# io-board-c-6.net
KiCad netlist of a schematic drawn in EAGLE
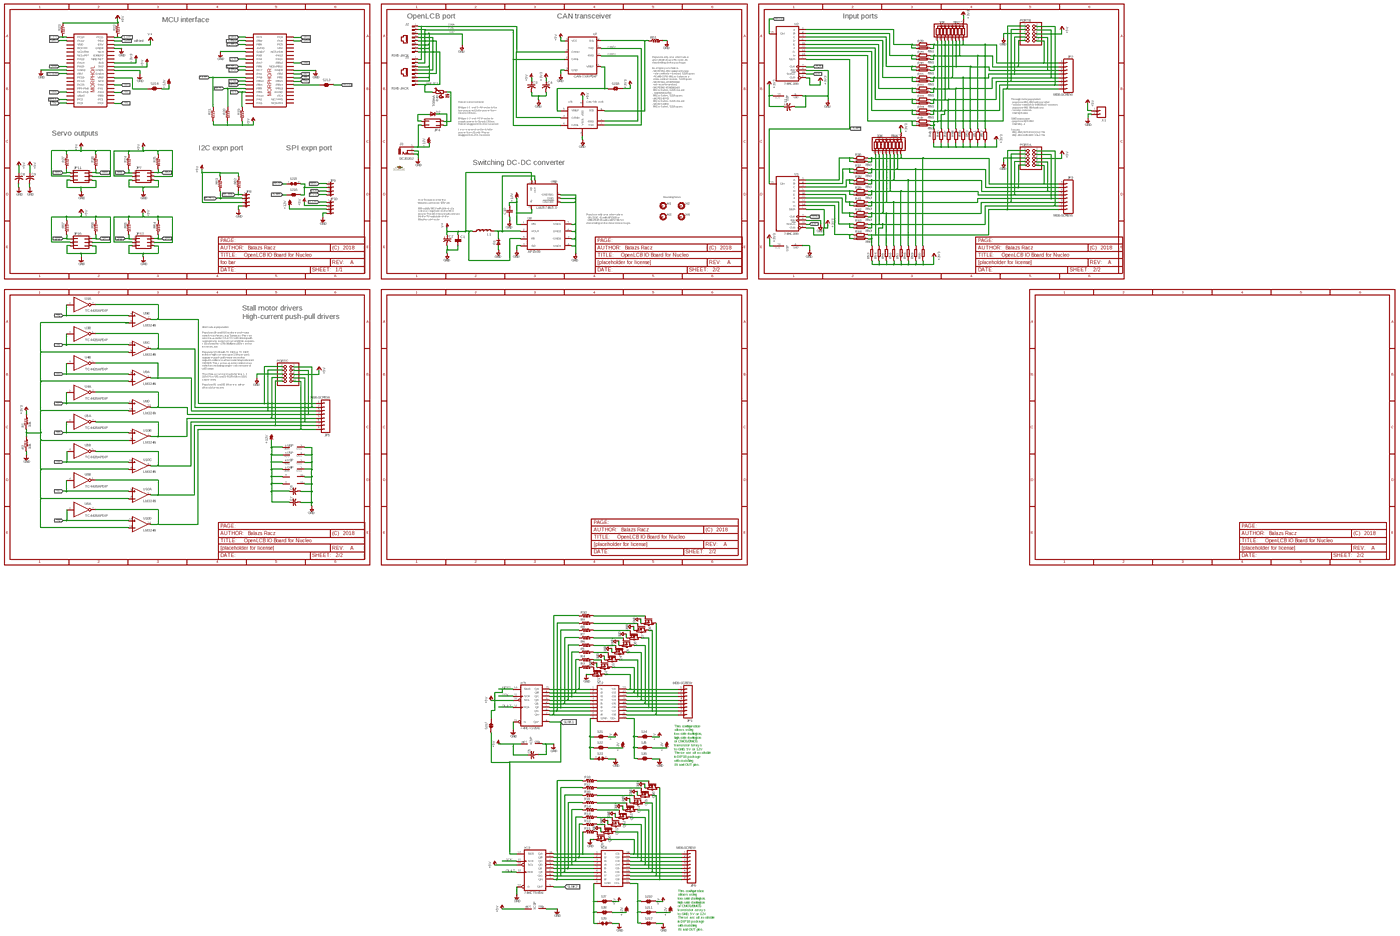
[diagram p0: schematic, sheet 1, overview]
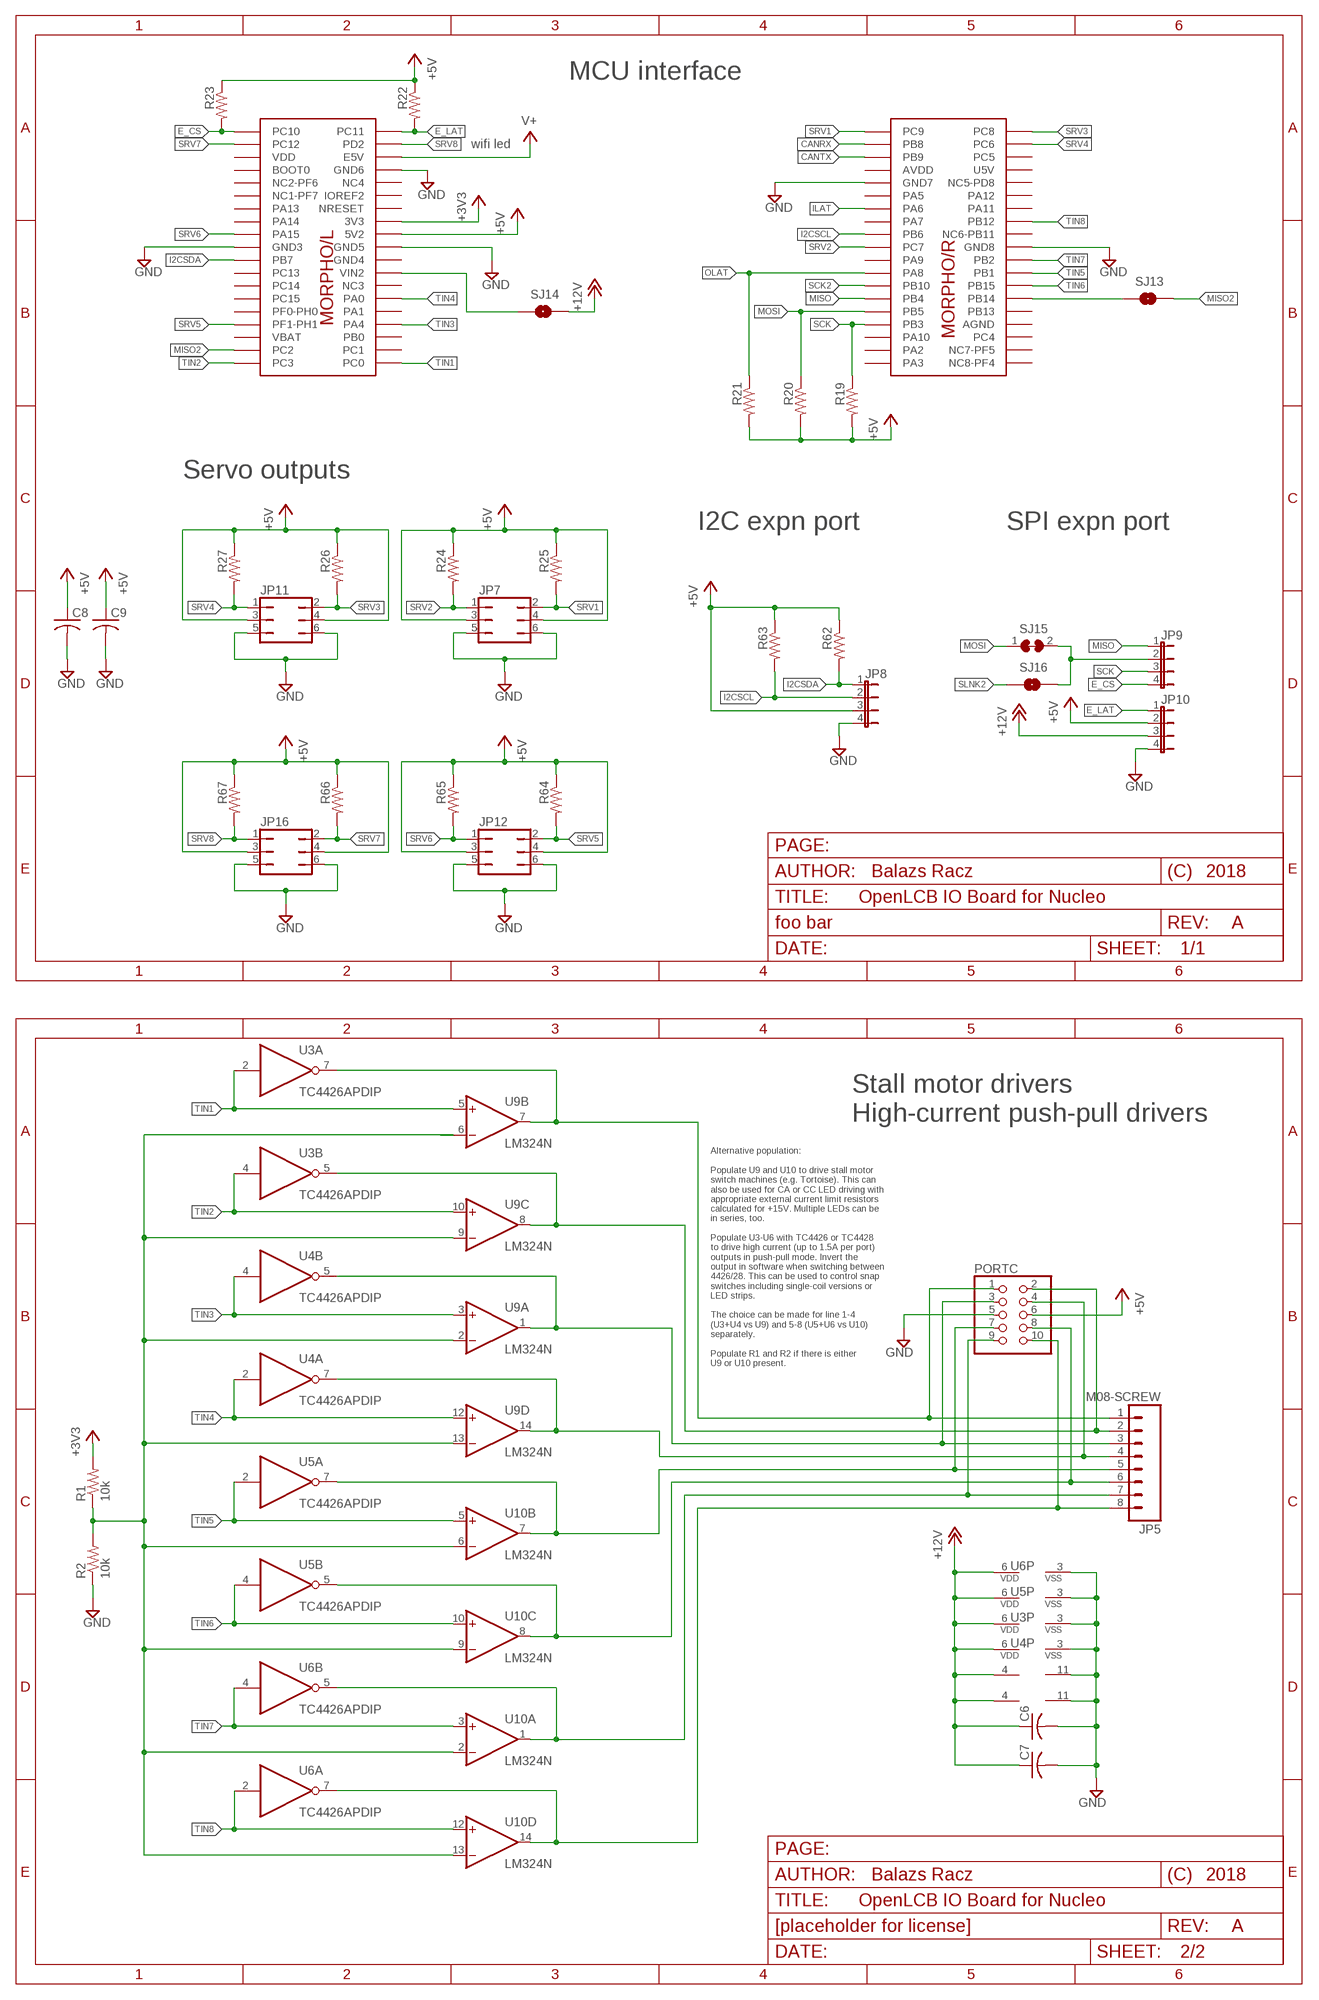
[diagram p1: schematic, sheet 1, part 1 of 4]
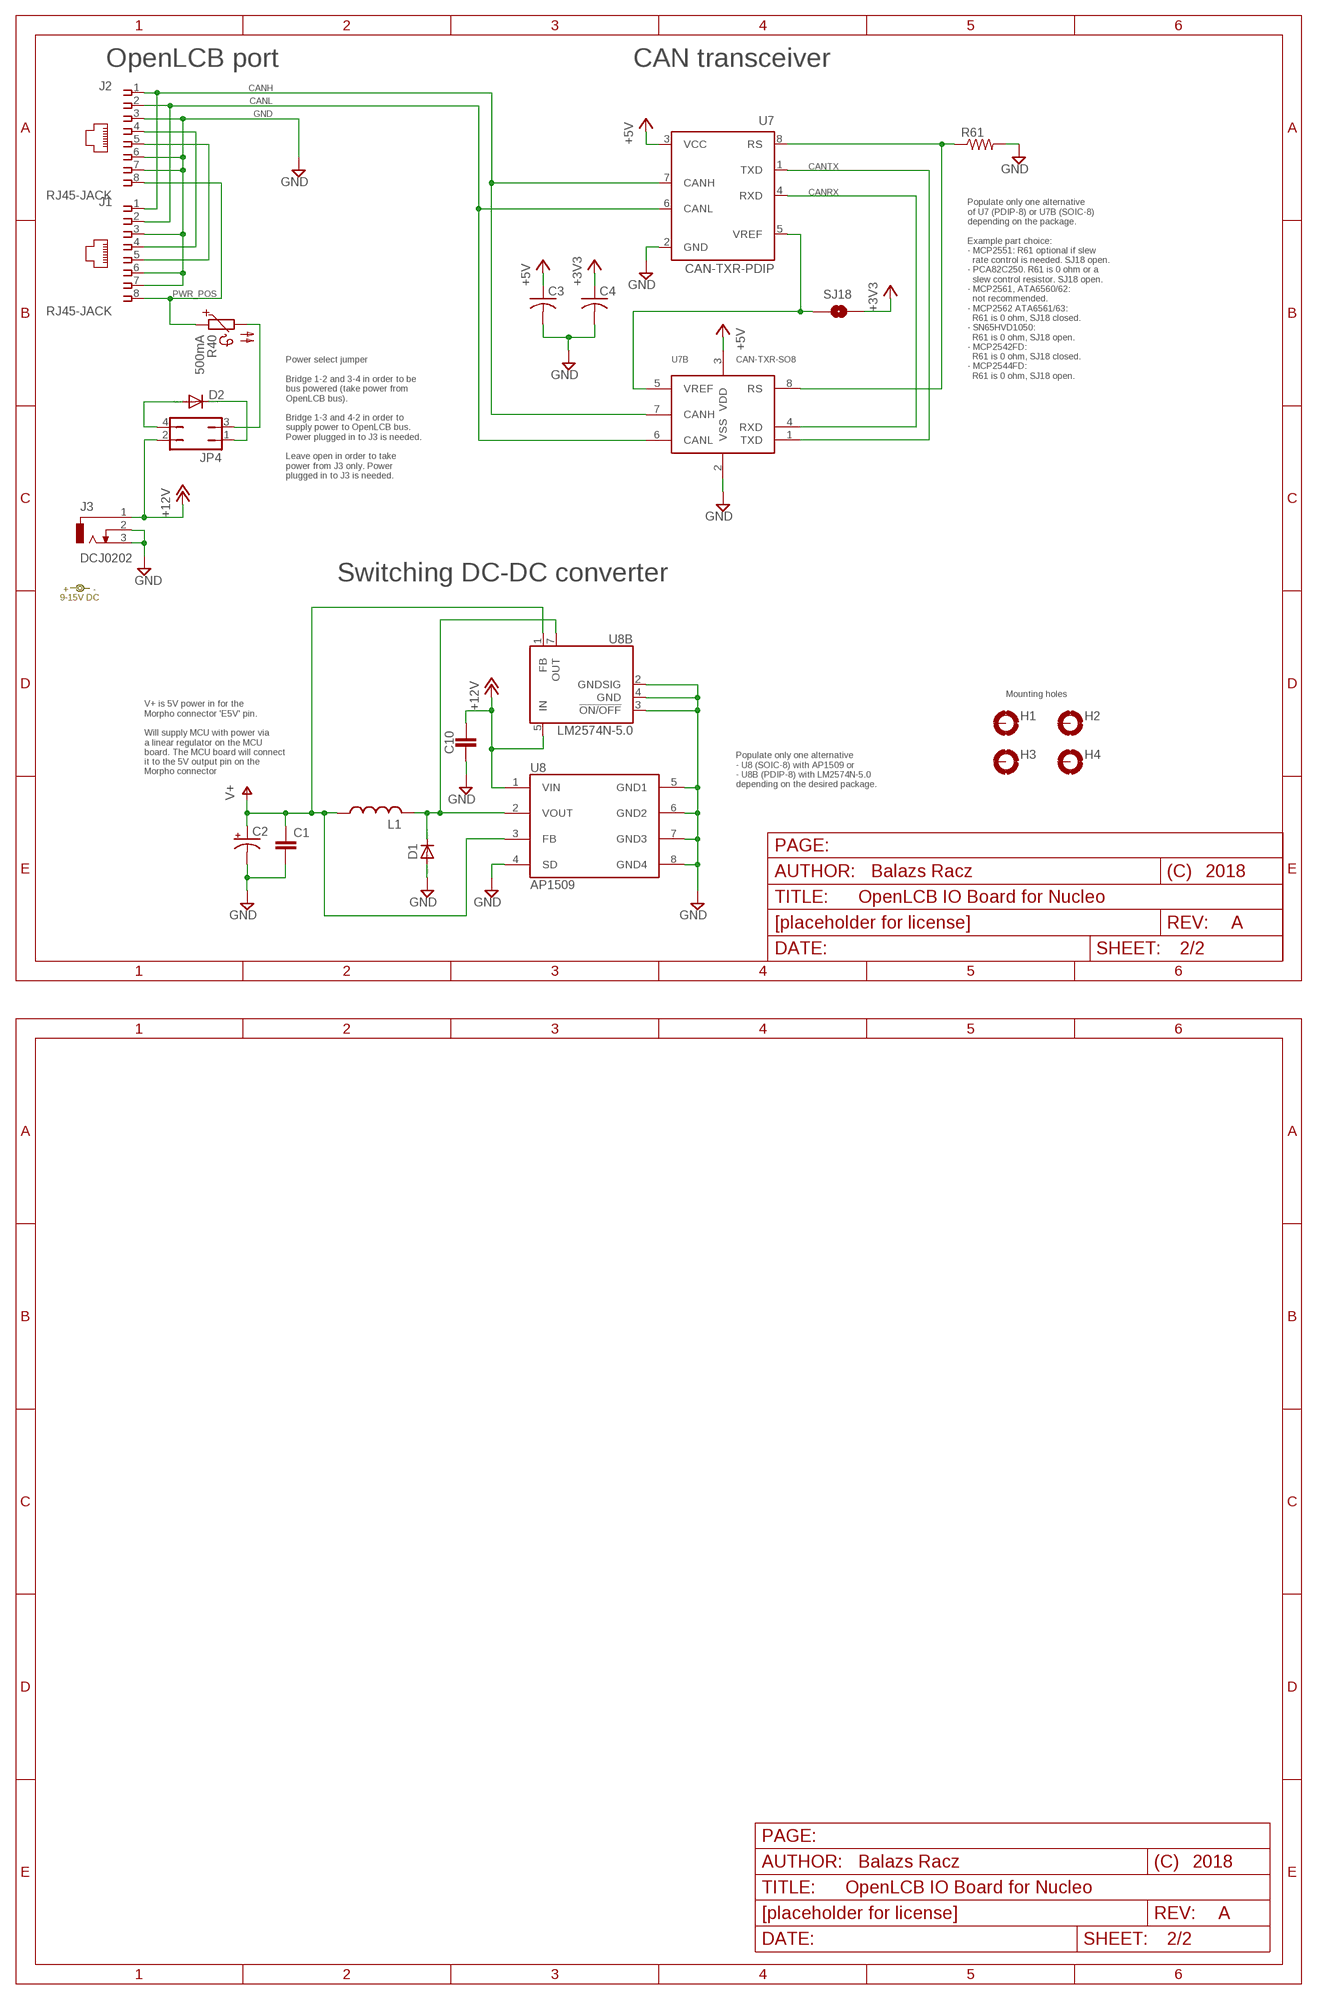
[diagram p2: schematic, sheet 1, part 2 of 4]
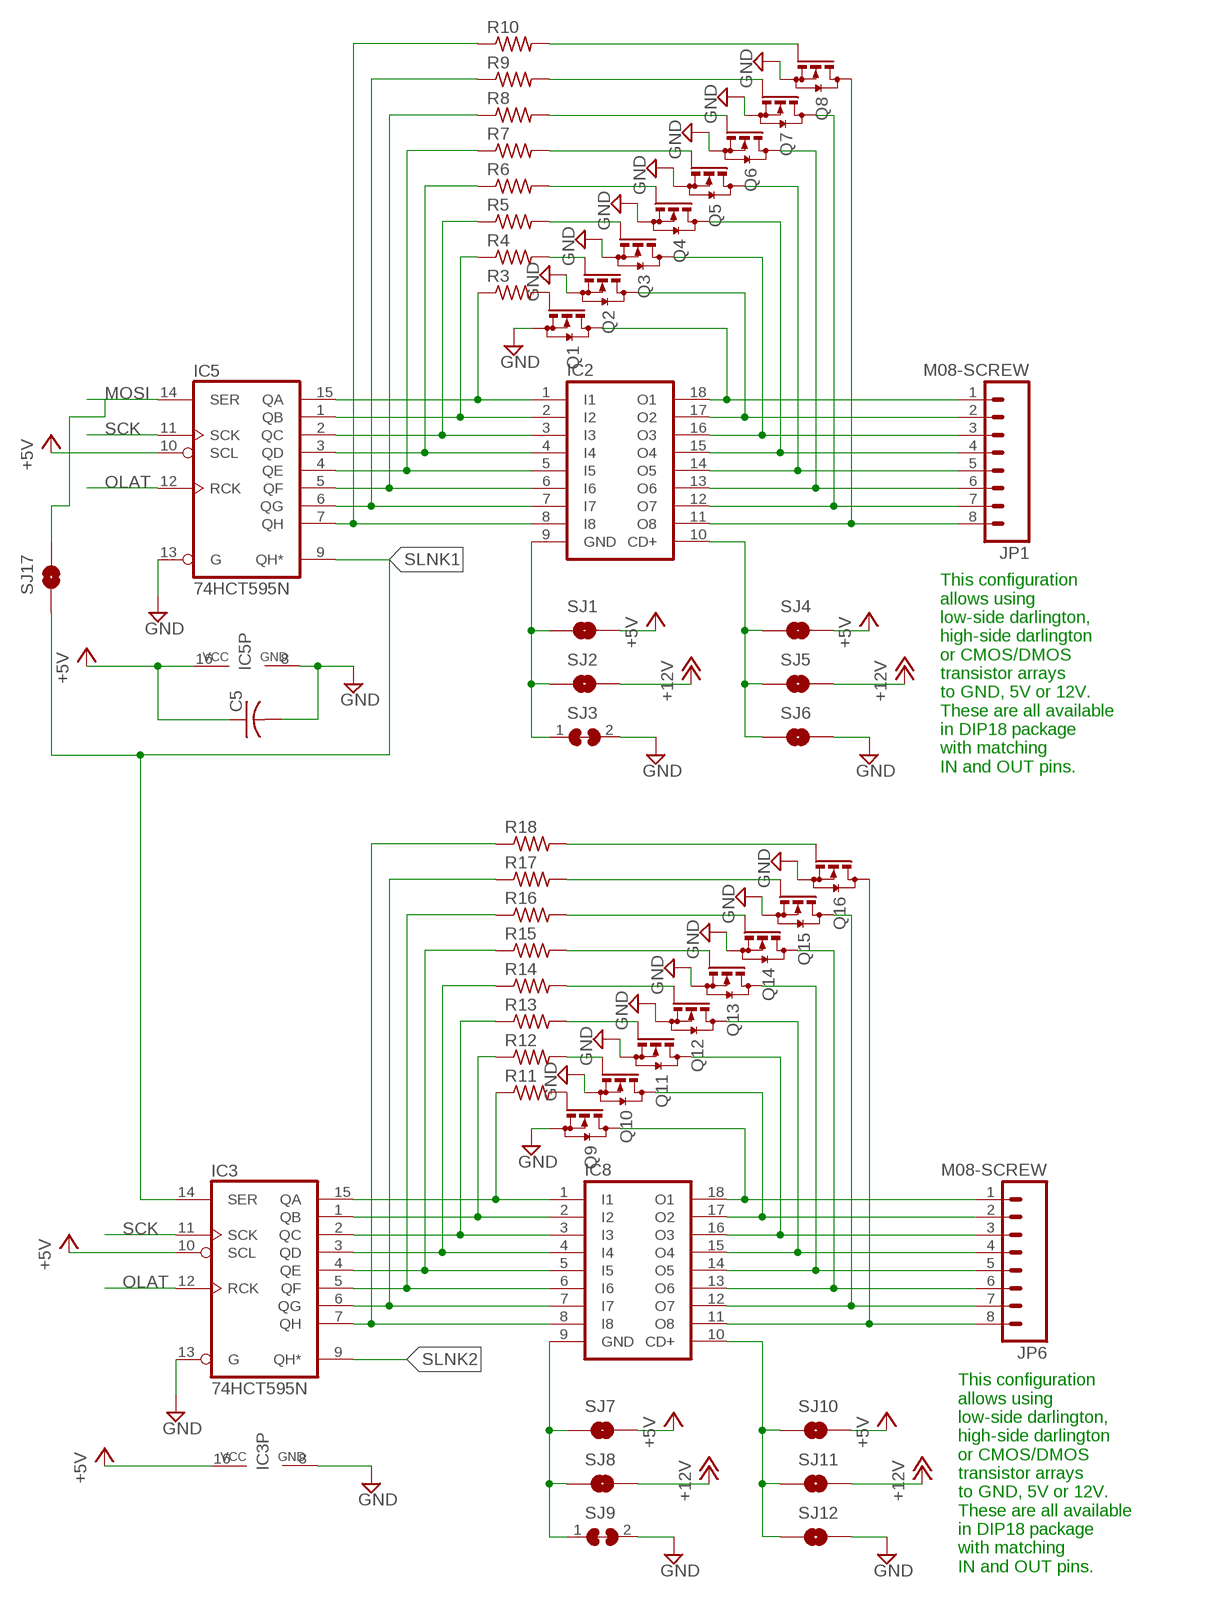
[diagram p3: schematic, sheet 1, part 3 of 4]
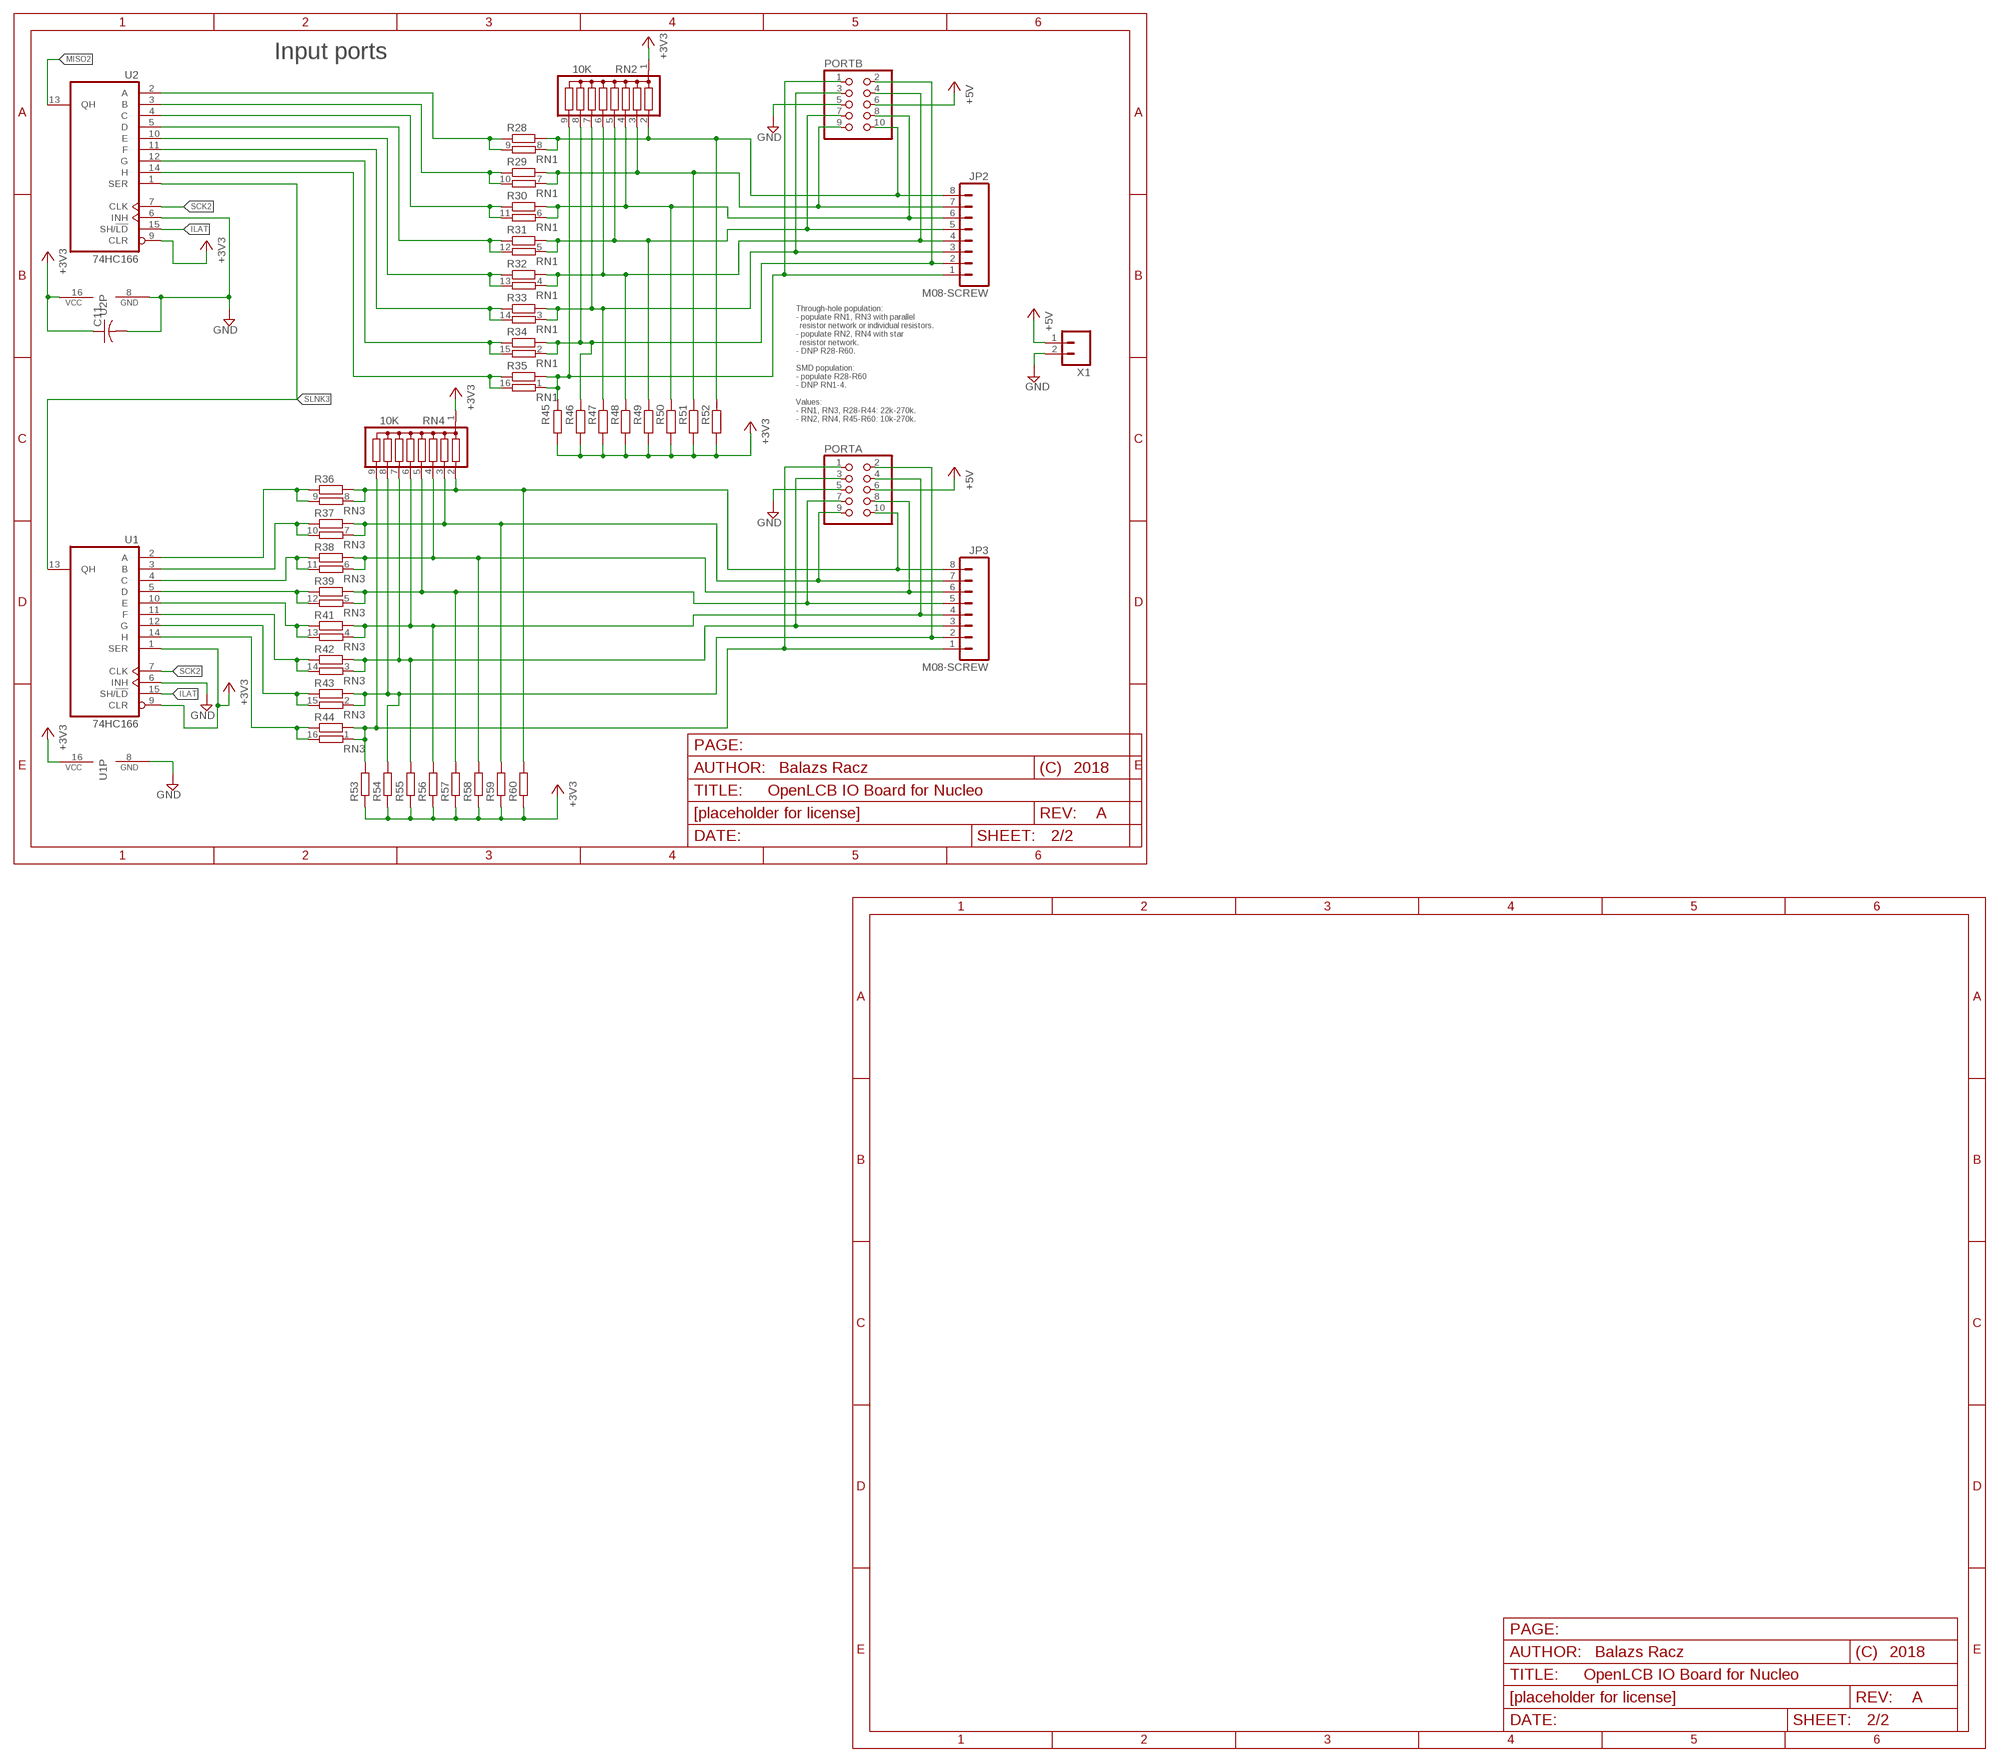
[diagram p4: schematic, sheet 1, part 4 of 4]

(export (version "E")
  (design (tool "Eeschema 10.0.6"))
  (components
    (comp (ref "+12V")
      (value "9-15V DC")
      (footprint "eagle-import:POWER_USAGE")
      (libsource (lib "eagle-import") (part "DOC-POWER_LABEL"))
    )
    (comp (ref "C1")
      (value "C-EUC1206")
      (footprint "eagle-import:C1206")
      (libsource (lib "eagle-import") (part "C-EUC1206"))
    )
    (comp (ref "C2")
      (value "CPOL-USE2.5-5")
      (footprint "eagle-import:E2,5-5")
      (libsource (lib "eagle-import") (part "CPOL-USE2.5-5"))
    )
    (comp (ref "C3")
      (value "C-USC0805")
      (footprint "eagle-import:C0805")
      (libsource (lib "eagle-import") (part "C-USC0805"))
    )
    (comp (ref "C4")
      (value "C-USC0805")
      (footprint "eagle-import:C0805")
      (libsource (lib "eagle-import") (part "C-USC0805"))
    )
    (comp (ref "C5")
      (value "C-USC0805")
      (footprint "eagle-import:C0805")
      (libsource (lib "eagle-import") (part "C-USC0805"))
    )
    (comp (ref "C6")
      (value "C-USC1206")
      (footprint "eagle-import:C1206")
      (libsource (lib "eagle-import") (part "C-USC1206"))
    )
    (comp (ref "C7")
      (value "C-USC1206")
      (footprint "eagle-import:C1206")
      (libsource (lib "eagle-import") (part "C-USC1206"))
    )
    (comp (ref "C8")
      (value "C-USC1206")
      (footprint "eagle-import:C1206")
      (libsource (lib "eagle-import") (part "C-USC1206"))
    )
    (comp (ref "C9")
      (value "C-USC1206")
      (footprint "eagle-import:C1206")
      (libsource (lib "eagle-import") (part "C-USC1206"))
    )
    (comp (ref "C10")
      (value "C-EUC1206")
      (footprint "eagle-import:C1206")
      (libsource (lib "eagle-import") (part "C-EUC1206"))
    )
    (comp (ref "C11")
      (value "C-USC0805")
      (footprint "eagle-import:C0805")
      (libsource (lib "eagle-import") (part "C-USC0805"))
    )
    (comp (ref "D1")
      (value "DIODE-DO41-7.6")
      (footprint "eagle-import:DO41-7.6")
      (libsource (lib "eagle-import") (part "DIODE-DO41-7.6"))
    )
    (comp (ref "D2")
      (value "DIODE-DO41-7.6")
      (footprint "eagle-import:DO41-7.6")
      (libsource (lib "eagle-import") (part "DIODE-DO41-7.6"))
    )
    (comp (ref "H1")
      (value "MOUNT-PAD-ROUND3.3")
      (footprint "eagle-import:3,3-PAD")
      (libsource (lib "eagle-import") (part "MOUNT-PAD-ROUND3.3"))
    )
    (comp (ref "H2")
      (value "MOUNT-PAD-ROUND3.3")
      (footprint "eagle-import:3,3-PAD")
      (libsource (lib "eagle-import") (part "MOUNT-PAD-ROUND3.3"))
    )
    (comp (ref "H3")
      (value "MOUNT-PAD-ROUND3.3")
      (footprint "eagle-import:3,3-PAD")
      (libsource (lib "eagle-import") (part "MOUNT-PAD-ROUND3.3"))
    )
    (comp (ref "H4")
      (value "MOUNT-PAD-ROUND3.3")
      (footprint "eagle-import:3,3-PAD")
      (libsource (lib "eagle-import") (part "MOUNT-PAD-ROUND3.3"))
    )
    (comp (ref "IC2")
      (value "ULN2803A")
      (footprint "eagle-import:DIL18-THIN")
      (libsource (lib "eagle-import") (part "ULN2803A"))
    )
    (comp (ref "IC3")
      (value "74HCT595N")
      (footprint "eagle-import:DIL16")
      (libsource (lib "eagle-import") (part "74595NHCT"))
    )
    (comp (ref "IC5")
      (value "74HCT595N")
      (footprint "eagle-import:DIL16")
      (libsource (lib "eagle-import") (part "74595NHCT"))
    )
    (comp (ref "IC8")
      (value "ULN2803A")
      (footprint "eagle-import:DIL18-THIN")
      (libsource (lib "eagle-import") (part "ULN2803A"))
    )
    (comp (ref "J1")
      (value "RJ45-JACK")
      (footprint "eagle-import:RJ45-PULSE-E5J88")
      (libsource (lib "eagle-import") (part "RJ45-JACKRJ45-PULSE-E5J00"))
    )
    (comp (ref "J2")
      (value "RJ45-JACK")
      (footprint "eagle-import:RJ45-PULSE-E5J88")
      (libsource (lib "eagle-import") (part "RJ45-JACKRJ45-PULSE-E5J00"))
    )
    (comp (ref "J3")
      (value "DCJ0202")
      (footprint "eagle-import:DCJ0202")
      (libsource (lib "eagle-import") (part "DCJ0202"))
    )
    (comp (ref "JP1")
      (value "M08-SCREW")
      (footprint "eagle-import:1X08_TERMINAL")
      (libsource (lib "eagle-import") (part "M08-SCREW"))
    )
    (comp (ref "JP2")
      (value "M08-SCREW")
      (footprint "eagle-import:1X08_TERMINAL")
      (libsource (lib "eagle-import") (part "M08-SCREW"))
    )
    (comp (ref "JP3")
      (value "M08-SCREW")
      (footprint "eagle-import:1X08_TERMINAL")
      (libsource (lib "eagle-import") (part "M08-SCREW"))
    )
    (comp (ref "JP4")
      (value "JP2Q")
      (footprint "eagle-import:JP2Q")
      (libsource (lib "eagle-import") (part "JP2Q"))
    )
    (comp (ref "JP5")
      (value "M08-SCREW")
      (footprint "eagle-import:1X08_TERMINAL")
      (libsource (lib "eagle-import") (part "M08-SCREW"))
    )
    (comp (ref "JP6")
      (value "M08-SCREW")
      (footprint "eagle-import:1X08_TERMINAL")
      (libsource (lib "eagle-import") (part "M08-SCREW"))
    )
    (comp (ref "JP7")
      (value "JP3Q")
      (footprint "eagle-import:JP3Q")
      (libsource (lib "eagle-import") (part "JP3Q"))
    )
    (comp (ref "JP8")
      (value "JP4-FLAT")
      (footprint "eagle-import:JP4F")
      (libsource (lib "eagle-import") (part "JP4-FLAT"))
    )
    (comp (ref "JP9")
      (value "JP4-FLAT")
      (footprint "eagle-import:JP4F")
      (libsource (lib "eagle-import") (part "JP4-FLAT"))
    )
    (comp (ref "JP10")
      (value "JP4-FLAT")
      (footprint "eagle-import:JP4F")
      (libsource (lib "eagle-import") (part "JP4-FLAT"))
    )
    (comp (ref "JP11")
      (value "JP3Q")
      (footprint "eagle-import:JP3Q")
      (libsource (lib "eagle-import") (part "JP3Q"))
    )
    (comp (ref "JP12")
      (value "JP3Q")
      (footprint "eagle-import:JP3Q")
      (libsource (lib "eagle-import") (part "JP3Q"))
    )
    (comp (ref "JP16")
      (value "JP3Q")
      (footprint "eagle-import:JP3Q")
      (libsource (lib "eagle-import") (part "JP3Q"))
    )
    (comp (ref "L1")
      (value "L-US")
      (footprint "eagle-import:L5-8,5")
      (libsource (lib "eagle-import") (part "L-US"))
    )
    (comp (ref "PORTA")
      (value "PINHD-2X5CN")
      (footprint "eagle-import:CON10M")
      (libsource (lib "eagle-import") (part "PINHD-2X5CN"))
    )
    (comp (ref "PORTB")
      (value "PINHD-2X5CN")
      (footprint "eagle-import:CON10M")
      (libsource (lib "eagle-import") (part "PINHD-2X5CN"))
    )
    (comp (ref "PORTC")
      (value "PINHD-2X5CN")
      (footprint "eagle-import:CON10M")
      (libsource (lib "eagle-import") (part "PINHD-2X5CN"))
    )
    (comp (ref "Q1")
      (value "BSS123")
      (footprint "eagle-import:SOT23")
      (libsource (lib "eagle-import") (part "BSS123"))
    )
    (comp (ref "Q2")
      (value "BSS123")
      (footprint "eagle-import:SOT23")
      (libsource (lib "eagle-import") (part "BSS123"))
    )
    (comp (ref "Q3")
      (value "BSS123")
      (footprint "eagle-import:SOT23")
      (libsource (lib "eagle-import") (part "BSS123"))
    )
    (comp (ref "Q4")
      (value "BSS123")
      (footprint "eagle-import:SOT23")
      (libsource (lib "eagle-import") (part "BSS123"))
    )
    (comp (ref "Q5")
      (value "BSS123")
      (footprint "eagle-import:SOT23")
      (libsource (lib "eagle-import") (part "BSS123"))
    )
    (comp (ref "Q6")
      (value "BSS123")
      (footprint "eagle-import:SOT23")
      (libsource (lib "eagle-import") (part "BSS123"))
    )
    (comp (ref "Q7")
      (value "BSS123")
      (footprint "eagle-import:SOT23")
      (libsource (lib "eagle-import") (part "BSS123"))
    )
    (comp (ref "Q8")
      (value "BSS123")
      (footprint "eagle-import:SOT23")
      (libsource (lib "eagle-import") (part "BSS123"))
    )
    (comp (ref "Q9")
      (value "BSS123")
      (footprint "eagle-import:SOT23")
      (libsource (lib "eagle-import") (part "BSS123"))
    )
    (comp (ref "Q10")
      (value "BSS123")
      (footprint "eagle-import:SOT23")
      (libsource (lib "eagle-import") (part "BSS123"))
    )
    (comp (ref "Q11")
      (value "BSS123")
      (footprint "eagle-import:SOT23")
      (libsource (lib "eagle-import") (part "BSS123"))
    )
    (comp (ref "Q12")
      (value "BSS123")
      (footprint "eagle-import:SOT23")
      (libsource (lib "eagle-import") (part "BSS123"))
    )
    (comp (ref "Q13")
      (value "BSS123")
      (footprint "eagle-import:SOT23")
      (libsource (lib "eagle-import") (part "BSS123"))
    )
    (comp (ref "Q14")
      (value "BSS123")
      (footprint "eagle-import:SOT23")
      (libsource (lib "eagle-import") (part "BSS123"))
    )
    (comp (ref "Q15")
      (value "BSS123")
      (footprint "eagle-import:SOT23")
      (libsource (lib "eagle-import") (part "BSS123"))
    )
    (comp (ref "Q16")
      (value "BSS123")
      (footprint "eagle-import:SOT23")
      (libsource (lib "eagle-import") (part "BSS123"))
    )
    (comp (ref "R1")
      (value "10k")
      (footprint "eagle-import:R0805")
      (libsource (lib "eagle-import") (part "R-US_R0805"))
    )
    (comp (ref "R2")
      (value "10k")
      (footprint "eagle-import:R0805")
      (libsource (lib "eagle-import") (part "R-US_R0805"))
    )
    (comp (ref "R3")
      (value "R-US_R0603")
      (footprint "eagle-import:R0603")
      (libsource (lib "eagle-import") (part "R-US_R0603"))
    )
    (comp (ref "R4")
      (value "R-US_R0603")
      (footprint "eagle-import:R0603")
      (libsource (lib "eagle-import") (part "R-US_R0603"))
    )
    (comp (ref "R5")
      (value "R-US_R0603")
      (footprint "eagle-import:R0603")
      (libsource (lib "eagle-import") (part "R-US_R0603"))
    )
    (comp (ref "R6")
      (value "R-US_R0603")
      (footprint "eagle-import:R0603")
      (libsource (lib "eagle-import") (part "R-US_R0603"))
    )
    (comp (ref "R7")
      (value "R-US_R0603")
      (footprint "eagle-import:R0603")
      (libsource (lib "eagle-import") (part "R-US_R0603"))
    )
    (comp (ref "R8")
      (value "R-US_R0603")
      (footprint "eagle-import:R0603")
      (libsource (lib "eagle-import") (part "R-US_R0603"))
    )
    (comp (ref "R9")
      (value "R-US_R0603")
      (footprint "eagle-import:R0603")
      (libsource (lib "eagle-import") (part "R-US_R0603"))
    )
    (comp (ref "R10")
      (value "R-US_R0603")
      (footprint "eagle-import:R0603")
      (libsource (lib "eagle-import") (part "R-US_R0603"))
    )
    (comp (ref "R11")
      (value "R-US_R0603")
      (footprint "eagle-import:R0603")
      (libsource (lib "eagle-import") (part "R-US_R0603"))
    )
    (comp (ref "R12")
      (value "R-US_R0603")
      (footprint "eagle-import:R0603")
      (libsource (lib "eagle-import") (part "R-US_R0603"))
    )
    (comp (ref "R13")
      (value "R-US_R0603")
      (footprint "eagle-import:R0603")
      (libsource (lib "eagle-import") (part "R-US_R0603"))
    )
    (comp (ref "R14")
      (value "R-US_R0603")
      (footprint "eagle-import:R0603")
      (libsource (lib "eagle-import") (part "R-US_R0603"))
    )
    (comp (ref "R15")
      (value "R-US_R0603")
      (footprint "eagle-import:R0603")
      (libsource (lib "eagle-import") (part "R-US_R0603"))
    )
    (comp (ref "R16")
      (value "R-US_R0603")
      (footprint "eagle-import:R0603")
      (libsource (lib "eagle-import") (part "R-US_R0603"))
    )
    (comp (ref "R17")
      (value "R-US_R0603")
      (footprint "eagle-import:R0603")
      (libsource (lib "eagle-import") (part "R-US_R0603"))
    )
    (comp (ref "R18")
      (value "R-US_R0603")
      (footprint "eagle-import:R0603")
      (libsource (lib "eagle-import") (part "R-US_R0603"))
    )
    (comp (ref "R19")
      (value "R-US_R0805")
      (footprint "eagle-import:R0805")
      (libsource (lib "eagle-import") (part "rcl_334_R-US_R0805"))
    )
    (comp (ref "R20")
      (value "R-US_R0805")
      (footprint "eagle-import:R0805")
      (libsource (lib "eagle-import") (part "rcl_334_R-US_R0805"))
    )
    (comp (ref "R21")
      (value "R-US_R0805")
      (footprint "eagle-import:R0805")
      (libsource (lib "eagle-import") (part "rcl_334_R-US_R0805"))
    )
    (comp (ref "R22")
      (value "R-US_R0805")
      (footprint "eagle-import:R0805")
      (libsource (lib "eagle-import") (part "rcl_334_R-US_R0805"))
    )
    (comp (ref "R23")
      (value "R-US_R0805")
      (footprint "eagle-import:R0805")
      (libsource (lib "eagle-import") (part "rcl_334_R-US_R0805"))
    )
    (comp (ref "R24")
      (value "R-US_R0805")
      (footprint "eagle-import:R0805")
      (libsource (lib "eagle-import") (part "rcl_334_R-US_R0805"))
    )
    (comp (ref "R25")
      (value "R-US_R0805")
      (footprint "eagle-import:R0805")
      (libsource (lib "eagle-import") (part "rcl_334_R-US_R0805"))
    )
    (comp (ref "R26")
      (value "R-US_R0805")
      (footprint "eagle-import:R0805")
      (libsource (lib "eagle-import") (part "rcl_334_R-US_R0805"))
    )
    (comp (ref "R27")
      (value "R-US_R0805")
      (footprint "eagle-import:R0805")
      (libsource (lib "eagle-import") (part "rcl_334_R-US_R0805"))
    )
    (comp (ref "R28")
      (value "R-EU_R0603")
      (footprint "eagle-import:R0603")
      (libsource (lib "eagle-import") (part "R-EU_R0603"))
    )
    (comp (ref "R29")
      (value "R-EU_R0603")
      (footprint "eagle-import:R0603")
      (libsource (lib "eagle-import") (part "R-EU_R0603"))
    )
    (comp (ref "R30")
      (value "R-EU_R0603")
      (footprint "eagle-import:R0603")
      (libsource (lib "eagle-import") (part "R-EU_R0603"))
    )
    (comp (ref "R31")
      (value "R-EU_R0603")
      (footprint "eagle-import:R0603")
      (libsource (lib "eagle-import") (part "R-EU_R0603"))
    )
    (comp (ref "R32")
      (value "R-EU_R0603")
      (footprint "eagle-import:R0603")
      (libsource (lib "eagle-import") (part "R-EU_R0603"))
    )
    (comp (ref "R33")
      (value "R-EU_R0603")
      (footprint "eagle-import:R0603")
      (libsource (lib "eagle-import") (part "R-EU_R0603"))
    )
    (comp (ref "R34")
      (value "R-EU_R0603")
      (footprint "eagle-import:R0603")
      (libsource (lib "eagle-import") (part "R-EU_R0603"))
    )
    (comp (ref "R35")
      (value "R-EU_R0603")
      (footprint "eagle-import:R0603")
      (libsource (lib "eagle-import") (part "R-EU_R0603"))
    )
    (comp (ref "R36")
      (value "R-EU_R0603")
      (footprint "eagle-import:R0603")
      (libsource (lib "eagle-import") (part "R-EU_R0603"))
    )
    (comp (ref "R37")
      (value "R-EU_R0603")
      (footprint "eagle-import:R0603")
      (libsource (lib "eagle-import") (part "R-EU_R0603"))
    )
    (comp (ref "R38")
      (value "R-EU_R0603")
      (footprint "eagle-import:R0603")
      (libsource (lib "eagle-import") (part "R-EU_R0603"))
    )
    (comp (ref "R39")
      (value "R-EU_R0603")
      (footprint "eagle-import:R0603")
      (libsource (lib "eagle-import") (part "R-EU_R0603"))
    )
    (comp (ref "R40")
      (value "500mA")
      (footprint "eagle-import:PTC1812")
      (libsource (lib "eagle-import") (part "PTC_1812"))
    )
    (comp (ref "R41")
      (value "R-EU_R0603")
      (footprint "eagle-import:R0603")
      (libsource (lib "eagle-import") (part "R-EU_R0603"))
    )
    (comp (ref "R42")
      (value "R-EU_R0603")
      (footprint "eagle-import:R0603")
      (libsource (lib "eagle-import") (part "R-EU_R0603"))
    )
    (comp (ref "R43")
      (value "R-EU_R0603")
      (footprint "eagle-import:R0603")
      (libsource (lib "eagle-import") (part "R-EU_R0603"))
    )
    (comp (ref "R44")
      (value "R-EU_R0603")
      (footprint "eagle-import:R0603")
      (libsource (lib "eagle-import") (part "R-EU_R0603"))
    )
    (comp (ref "R45")
      (value "R-EU_R0603")
      (footprint "eagle-import:R0603")
      (libsource (lib "eagle-import") (part "R-EU_R0603"))
    )
    (comp (ref "R46")
      (value "R-EU_R0603")
      (footprint "eagle-import:R0603")
      (libsource (lib "eagle-import") (part "R-EU_R0603"))
    )
    (comp (ref "R47")
      (value "R-EU_R0603")
      (footprint "eagle-import:R0603")
      (libsource (lib "eagle-import") (part "R-EU_R0603"))
    )
    (comp (ref "R48")
      (value "R-EU_R0603")
      (footprint "eagle-import:R0603")
      (libsource (lib "eagle-import") (part "R-EU_R0603"))
    )
    (comp (ref "R49")
      (value "R-EU_R0603")
      (footprint "eagle-import:R0603")
      (libsource (lib "eagle-import") (part "R-EU_R0603"))
    )
    (comp (ref "R50")
      (value "R-EU_R0603")
      (footprint "eagle-import:R0603")
      (libsource (lib "eagle-import") (part "R-EU_R0603"))
    )
    (comp (ref "R51")
      (value "R-EU_R0603")
      (footprint "eagle-import:R0603")
      (libsource (lib "eagle-import") (part "R-EU_R0603"))
    )
    (comp (ref "R52")
      (value "R-EU_R0603")
      (footprint "eagle-import:R0603")
      (libsource (lib "eagle-import") (part "R-EU_R0603"))
    )
    (comp (ref "R53")
      (value "R-EU_R0603")
      (footprint "eagle-import:R0603")
      (libsource (lib "eagle-import") (part "R-EU_R0603"))
    )
    (comp (ref "R54")
      (value "R-EU_R0603")
      (footprint "eagle-import:R0603")
      (libsource (lib "eagle-import") (part "R-EU_R0603"))
    )
    (comp (ref "R55")
      (value "R-EU_R0603")
      (footprint "eagle-import:R0603")
      (libsource (lib "eagle-import") (part "R-EU_R0603"))
    )
    (comp (ref "R56")
      (value "R-EU_R0603")
      (footprint "eagle-import:R0603")
      (libsource (lib "eagle-import") (part "R-EU_R0603"))
    )
    (comp (ref "R57")
      (value "R-EU_R0603")
      (footprint "eagle-import:R0603")
      (libsource (lib "eagle-import") (part "R-EU_R0603"))
    )
    (comp (ref "R58")
      (value "R-EU_R0603")
      (footprint "eagle-import:R0603")
      (libsource (lib "eagle-import") (part "R-EU_R0603"))
    )
    (comp (ref "R59")
      (value "R-EU_R0603")
      (footprint "eagle-import:R0603")
      (libsource (lib "eagle-import") (part "R-EU_R0603"))
    )
    (comp (ref "R60")
      (value "R-EU_R0603")
      (footprint "eagle-import:R0603")
      (libsource (lib "eagle-import") (part "R-EU_R0603"))
    )
    (comp (ref "R61")
      (value "R-US_R0805")
      (footprint "eagle-import:R0805")
      (libsource (lib "eagle-import") (part "rcl_334_R-US_R0805"))
    )
    (comp (ref "R62")
      (value "R-US_R0805")
      (footprint "eagle-import:R0805")
      (libsource (lib "eagle-import") (part "rcl_334_R-US_R0805"))
    )
    (comp (ref "R63")
      (value "R-US_R0805")
      (footprint "eagle-import:R0805")
      (libsource (lib "eagle-import") (part "rcl_334_R-US_R0805"))
    )
    (comp (ref "R64")
      (value "R-US_R0805")
      (footprint "eagle-import:R0805")
      (libsource (lib "eagle-import") (part "rcl_334_R-US_R0805"))
    )
    (comp (ref "R65")
      (value "R-US_R0805")
      (footprint "eagle-import:R0805")
      (libsource (lib "eagle-import") (part "rcl_334_R-US_R0805"))
    )
    (comp (ref "R66")
      (value "R-US_R0805")
      (footprint "eagle-import:R0805")
      (libsource (lib "eagle-import") (part "rcl_334_R-US_R0805"))
    )
    (comp (ref "R67")
      (value "R-US_R0805")
      (footprint "eagle-import:R0805")
      (libsource (lib "eagle-import") (part "rcl_334_R-US_R0805"))
    )
    (comp (ref "RN1")
      (value "8R-P")
      (footprint "eagle-import:DIL16")
      (libsource (lib "eagle-import") (part "8R-P"))
    )
    (comp (ref "RN2")
      (value "10K")
      (footprint "eagle-import:SIL9")
      (libsource (lib "eagle-import") (part "G08R"))
    )
    (comp (ref "RN3")
      (value "8R-P")
      (footprint "eagle-import:DIL16")
      (libsource (lib "eagle-import") (part "8R-P"))
    )
    (comp (ref "RN4")
      (value "10K")
      (footprint "eagle-import:SIL9")
      (libsource (lib "eagle-import") (part "G08R"))
    )
    (comp (ref "SJ1")
      (value "SJRND2")
      (footprint "eagle-import:SJ_RND2")
      (libsource (lib "eagle-import") (part "SJRND2"))
    )
    (comp (ref "SJ2")
      (value "SJRND2")
      (footprint "eagle-import:SJ_RND2")
      (libsource (lib "eagle-import") (part "SJRND2"))
    )
    (comp (ref "SJ3")
      (value "SJ-C")
      (footprint "eagle-import:SJW-C")
      (libsource (lib "eagle-import") (part "SJ-C"))
    )
    (comp (ref "SJ4")
      (value "SJRND2")
      (footprint "eagle-import:SJ_RND2")
      (libsource (lib "eagle-import") (part "SJRND2"))
    )
    (comp (ref "SJ5")
      (value "SJRND2")
      (footprint "eagle-import:SJ_RND2")
      (libsource (lib "eagle-import") (part "SJRND2"))
    )
    (comp (ref "SJ6")
      (value "SJRND2")
      (footprint "eagle-import:SJ_RND2")
      (libsource (lib "eagle-import") (part "SJRND2"))
    )
    (comp (ref "SJ7")
      (value "SJRND2")
      (footprint "eagle-import:SJ_RND2")
      (libsource (lib "eagle-import") (part "SJRND2"))
    )
    (comp (ref "SJ8")
      (value "SJRND2")
      (footprint "eagle-import:SJ_RND2")
      (libsource (lib "eagle-import") (part "SJRND2"))
    )
    (comp (ref "SJ9")
      (value "SJ-C")
      (footprint "eagle-import:SJW-C")
      (libsource (lib "eagle-import") (part "SJ-C"))
    )
    (comp (ref "SJ10")
      (value "SJRND2")
      (footprint "eagle-import:SJ_RND2")
      (libsource (lib "eagle-import") (part "SJRND2"))
    )
    (comp (ref "SJ11")
      (value "SJRND2")
      (footprint "eagle-import:SJ_RND2")
      (libsource (lib "eagle-import") (part "SJRND2"))
    )
    (comp (ref "SJ12")
      (value "SJRND2")
      (footprint "eagle-import:SJ_RND2")
      (libsource (lib "eagle-import") (part "SJRND2"))
    )
    (comp (ref "SJ13")
      (value "SJRND2")
      (footprint "eagle-import:SJ_RND2")
      (libsource (lib "eagle-import") (part "SJRND2"))
    )
    (comp (ref "SJ14")
      (value "SJRND2")
      (footprint "eagle-import:SJ_RND2")
      (libsource (lib "eagle-import") (part "SJRND2"))
    )
    (comp (ref "SJ15")
      (value "SJ-C")
      (footprint "eagle-import:SJW-C")
      (libsource (lib "eagle-import") (part "SJ-C"))
    )
    (comp (ref "SJ16")
      (value "SJRND2")
      (footprint "eagle-import:SJ_RND2")
      (libsource (lib "eagle-import") (part "SJRND2"))
    )
    (comp (ref "SJ17")
      (value "SJRND2")
      (footprint "eagle-import:SJ_RND2")
      (libsource (lib "eagle-import") (part "SJRND2"))
    )
    (comp (ref "SJ18")
      (value "SJRND2")
      (footprint "eagle-import:SJ_RND2")
      (libsource (lib "eagle-import") (part "SJRND2"))
    )
    (comp (ref "U$1")
      (value "NUCLEO_64_GENERIC")
      (footprint "eagle-import:NUCLEO_BRD_BASE64")
      (libsource (lib "eagle-import") (part "NUCLEO_64_GENERIC"))
    )
    (comp (ref "U1")
      (value "74HC166")
      (footprint "eagle-import:DIL16")
      (libsource (lib "eagle-import") (part "74166N"))
    )
    (comp (ref "U2")
      (value "74HC166")
      (footprint "eagle-import:DIL16")
      (libsource (lib "eagle-import") (part "74166N"))
    )
    (comp (ref "U3")
      (value "TC4426APDIP")
      (footprint "eagle-import:DIL08-LONG")
      (libsource (lib "eagle-import") (part "TC4426APDIP"))
    )
    (comp (ref "U4")
      (value "TC4426APDIP")
      (footprint "eagle-import:DIL08-LONG")
      (libsource (lib "eagle-import") (part "TC4426APDIP"))
    )
    (comp (ref "U5")
      (value "TC4426APDIP")
      (footprint "eagle-import:DIL08-LONG")
      (libsource (lib "eagle-import") (part "TC4426APDIP"))
    )
    (comp (ref "U6")
      (value "TC4426APDIP")
      (footprint "eagle-import:DIL08-LONG")
      (libsource (lib "eagle-import") (part "TC4426APDIP"))
    )
    (comp (ref "U7")
      (value "CAN-TXR-PDIP")
      (footprint "eagle-import:DIL08")
      (libsource (lib "eagle-import") (part "PCA82C250"))
    )
    (comp (ref "U7B")
      (value "CAN-TXR-SO8")
      (footprint "eagle-import:SO-08")
      (libsource (lib "eagle-import") (part "MCP2551-SN"))
    )
    (comp (ref "U8")
      (value "AP1509")
      (footprint "eagle-import:SO-08")
      (libsource (lib "eagle-import") (part "AP1509"))
    )
    (comp (ref "U8B")
      (value "LM2574N-5.0")
      (footprint "eagle-import:DIL08")
      (libsource (lib "eagle-import") (part "LM2574?-N5.0"))
    )
    (comp (ref "U9")
      (value "LM324N")
      (footprint "eagle-import:DIL14")
      (libsource (lib "eagle-import") (part "LM324N"))
    )
    (comp (ref "U10")
      (value "LM324N")
      (footprint "eagle-import:DIL14")
      (libsource (lib "eagle-import") (part "LM324N"))
    )
    (comp (ref "X1")
      (value "CONNECTOR-M023.5MM-LOCK")
      (footprint "eagle-import:SCREWTERMINAL-3.5MM-2_LOCK")
      (libsource (lib "eagle-import") (part "CONNECTOR-M023.5MM-LOCK"))
    )
  )
  (nets
    (net (code "1") (name "+3V3") (class "Default")
      (node (ref "C11") (pin "1") (pinfunction "1_1") (pintype "passive"))
      (node (ref "C4") (pin "1") (pinfunction "1_1") (pintype "passive"))
      (node (ref "R1") (pin "2") (pinfunction "2_2") (pintype "passive"))
      (node (ref "R45") (pin "1") (pinfunction "1_1") (pintype "passive"))
      (node (ref "R46") (pin "2") (pinfunction "2_2") (pintype "passive"))
      (node (ref "R47") (pin "2") (pinfunction "2_2") (pintype "passive"))
      (node (ref "R48") (pin "2") (pinfunction "2_2") (pintype "passive"))
      (node (ref "R49") (pin "2") (pinfunction "2_2") (pintype "passive"))
      (node (ref "R50") (pin "2") (pinfunction "2_2") (pintype "passive"))
      (node (ref "R51") (pin "2") (pinfunction "2_2") (pintype "passive"))
      (node (ref "R52") (pin "2") (pinfunction "2_2") (pintype "passive"))
      (node (ref "R53") (pin "1") (pinfunction "1_1") (pintype "passive"))
      (node (ref "R54") (pin "1") (pinfunction "1_1") (pintype "passive"))
      (node (ref "R55") (pin "1") (pinfunction "1_1") (pintype "passive"))
      (node (ref "R56") (pin "1") (pinfunction "1_1") (pintype "passive"))
      (node (ref "R57") (pin "1") (pinfunction "1_1") (pintype "passive"))
      (node (ref "R58") (pin "1") (pinfunction "1_1") (pintype "passive"))
      (node (ref "R59") (pin "1") (pinfunction "1_1") (pintype "passive"))
      (node (ref "R60") (pin "1") (pinfunction "1_1") (pintype "passive"))
      (node (ref "RN2") (pin "1") (pinfunction "1_1") (pintype "passive"))
      (node (ref "RN4") (pin "1") (pinfunction "1_1") (pintype "passive"))
      (node (ref "SJ18") (pin "P$1") (pinfunction "1_P$1") (pintype "passive"))
      (node (ref "U$1") (pin "3V3") (pinfunction "3V3_3V3") (pintype "power_in"))
      (node (ref "U1") (pin "1") (pinfunction "SER_1") (pintype "input"))
      (node (ref "U1") (pin "16") (pinfunction "VCC_16") (pintype "power_in"))
      (node (ref "U1") (pin "9") (pinfunction "CLR_9") (pintype "input"))
      (node (ref "U2") (pin "16") (pinfunction "VCC_16") (pintype "power_in"))
      (node (ref "U2") (pin "9") (pinfunction "CLR_9") (pintype "input"))
    )
    (net (code "2") (name "+5V") (class "Default")
      (node (ref "C3") (pin "1") (pinfunction "1_1") (pintype "passive"))
      (node (ref "C5") (pin "1") (pinfunction "1_1") (pintype "passive"))
      (node (ref "C8") (pin "1") (pinfunction "1_1") (pintype "passive"))
      (node (ref "C9") (pin "1") (pinfunction "1_1") (pintype "passive"))
      (node (ref "IC3") (pin "10") (pinfunction "SCL_10") (pintype "input"))
      (node (ref "IC3") (pin "16") (pinfunction "VCC_16") (pintype "power_in"))
      (node (ref "IC5") (pin "10") (pinfunction "SCL_10") (pintype "input"))
      (node (ref "IC5") (pin "16") (pinfunction "VCC_16") (pintype "power_in"))
      (node (ref "JP10") (pin "2") (pinfunction "2_2") (pintype "passive"))
      (node (ref "JP11") (pin "3") (pinfunction "3_3") (pintype "passive"))
      (node (ref "JP11") (pin "4") (pinfunction "4_4") (pintype "passive"))
      (node (ref "JP12") (pin "3") (pinfunction "3_3") (pintype "passive"))
      (node (ref "JP12") (pin "4") (pinfunction "4_4") (pintype "passive"))
      (node (ref "JP16") (pin "3") (pinfunction "3_3") (pintype "passive"))
      (node (ref "JP16") (pin "4") (pinfunction "4_4") (pintype "passive"))
      (node (ref "JP7") (pin "3") (pinfunction "3_3") (pintype "passive"))
      (node (ref "JP7") (pin "4") (pinfunction "4_4") (pintype "passive"))
      (node (ref "JP8") (pin "3") (pinfunction "3_3") (pintype "passive"))
      (node (ref "PORTA") (pin "6") (pinfunction "6_6") (pintype "passive"))
      (node (ref "PORTB") (pin "6") (pinfunction "6_6") (pintype "passive"))
      (node (ref "PORTC") (pin "6") (pinfunction "6_6") (pintype "passive"))
      (node (ref "R19") (pin "2") (pinfunction "2_2") (pintype "passive"))
      (node (ref "R20") (pin "2") (pinfunction "2_2") (pintype "passive"))
      (node (ref "R21") (pin "2") (pinfunction "2_2") (pintype "passive"))
      (node (ref "R22") (pin "1") (pinfunction "1_1") (pintype "passive"))
      (node (ref "R23") (pin "1") (pinfunction "1_1") (pintype "passive"))
      (node (ref "R24") (pin "1") (pinfunction "1_1") (pintype "passive"))
      (node (ref "R25") (pin "1") (pinfunction "1_1") (pintype "passive"))
      (node (ref "R26") (pin "1") (pinfunction "1_1") (pintype "passive"))
      (node (ref "R27") (pin "1") (pinfunction "1_1") (pintype "passive"))
      (node (ref "R62") (pin "1") (pinfunction "1_1") (pintype "passive"))
      (node (ref "R63") (pin "1") (pinfunction "1_1") (pintype "passive"))
      (node (ref "R64") (pin "1") (pinfunction "1_1") (pintype "passive"))
      (node (ref "R65") (pin "1") (pinfunction "1_1") (pintype "passive"))
      (node (ref "R66") (pin "1") (pinfunction "1_1") (pintype "passive"))
      (node (ref "R67") (pin "1") (pinfunction "1_1") (pintype "passive"))
      (node (ref "SJ1") (pin "P$2") (pinfunction "2_P$2") (pintype "passive"))
      (node (ref "SJ10") (pin "P$2") (pinfunction "2_P$2") (pintype "passive"))
      (node (ref "SJ4") (pin "P$2") (pinfunction "2_P$2") (pintype "passive"))
      (node (ref "SJ7") (pin "P$2") (pinfunction "2_P$2") (pintype "passive"))
      (node (ref "U$1") (pin "5V2") (pinfunction "5V2_5V2") (pintype "power_in"))
      (node (ref "U7") (pin "3") (pinfunction "VCC_3") (pintype "power_in"))
      (node (ref "U7B") (pin "3") (pinfunction "VDD_3") (pintype "power_in"))
      (node (ref "X1") (pin "1") (pinfunction "1_1") (pintype "passive"))
    )
    (net (code "3") (name "+12V") (class "Default")
      (node (ref "C10") (pin "1") (pinfunction "1_1") (pintype "passive"))
      (node (ref "C6") (pin "1") (pinfunction "1_1") (pintype "passive"))
      (node (ref "C7") (pin "1") (pinfunction "1_1") (pintype "passive"))
      (node (ref "J3") (pin "1") (pinfunction "1_1") (pintype "passive"))
      (node (ref "JP10") (pin "3") (pinfunction "3_3") (pintype "passive"))
      (node (ref "JP4") (pin "2") (pinfunction "2_2") (pintype "passive"))
      (node (ref "SJ11") (pin "P$2") (pinfunction "2_P$2") (pintype "passive"))
      (node (ref "SJ14") (pin "P$2") (pinfunction "2_P$2") (pintype "passive"))
      (node (ref "SJ2") (pin "P$2") (pinfunction "2_P$2") (pintype "passive"))
      (node (ref "SJ5") (pin "P$2") (pinfunction "2_P$2") (pintype "passive"))
      (node (ref "SJ8") (pin "P$2") (pinfunction "2_P$2") (pintype "passive"))
      (node (ref "U10") (pin "4") (pinfunction "V+_4") (pintype "power_in"))
      (node (ref "U3") (pin "6") (pinfunction "VDD_6") (pintype "power_in"))
      (node (ref "U4") (pin "6") (pinfunction "VDD_6") (pintype "power_in"))
      (node (ref "U5") (pin "6") (pinfunction "VDD_6") (pintype "power_in"))
      (node (ref "U6") (pin "6") (pinfunction "VDD_6") (pintype "power_in"))
      (node (ref "U8") (pin "1") (pinfunction "VIN_1") (pintype "bidirectional"))
      (node (ref "U8B") (pin "5") (pinfunction "IN_5") (pintype "input"))
      (node (ref "U9") (pin "4") (pinfunction "V+_4") (pintype "power_in"))
    )
    (net (code "4") (name "/AGND") (class "Default")
      (node (ref "U$1") (pin "AGND") (pinfunction "AGND_AGND") (pintype "power_in"))
    )
    (net (code "5") (name "/AVDD") (class "Default")
      (node (ref "U$1") (pin "AVDD") (pinfunction "AVDD_AVDD") (pintype "power_in"))
    )
    (net (code "6") (name "/CANH") (class "Default")
      (node (ref "J1") (pin "1") (pinfunction "1_1") (pintype "passive"))
      (node (ref "J2") (pin "1") (pinfunction "1_1") (pintype "passive"))
      (node (ref "U7") (pin "7") (pinfunction "CANH_7") (pintype "bidirectional"))
      (node (ref "U7B") (pin "7") (pinfunction "CANH_7") (pintype "bidirectional"))
    )
    (net (code "7") (name "/CANL") (class "Default")
      (node (ref "J1") (pin "2") (pinfunction "2_2") (pintype "passive"))
      (node (ref "J2") (pin "2") (pinfunction "2_2") (pintype "passive"))
      (node (ref "U7") (pin "6") (pinfunction "CANL_6") (pintype "bidirectional"))
      (node (ref "U7B") (pin "6") (pinfunction "CANL_6") (pintype "bidirectional"))
    )
    (net (code "8") (name "/GND4") (class "Default")
      (node (ref "U$1") (pin "GND4") (pinfunction "GND4_GND4") (pintype "power_in"))
    )
    (net (code "9") (name "/PWR_POS") (class "Default")
      (node (ref "J1") (pin "8") (pinfunction "8_8") (pintype "passive"))
      (node (ref "J2") (pin "8") (pinfunction "8_8") (pintype "passive"))
      (node (ref "R40") (pin "1") (pinfunction "1_1") (pintype "passive"))
    )
    (net (code "10") (name "/U5V") (class "Default")
      (node (ref "U$1") (pin "U5V") (pinfunction "U5V_U5V") (pintype "power_in"))
    )
    (net (code "11") (name "/VBAT") (class "Default")
      (node (ref "U$1") (pin "VBAT") (pinfunction "VBAT_VBAT") (pintype "power_in"))
    )
    (net (code "12") (name "/VDD") (class "Default")
      (node (ref "U$1") (pin "VDD") (pinfunction "VDD_VDD") (pintype "power_in"))
    )
    (net (code "13") (name "CANRX") (class "Default")
      (node (ref "U$1") (pin "PB8") (pinfunction "PB8_PB8") (pintype "bidirectional"))
      (node (ref "U7") (pin "4") (pinfunction "RXD_4") (pintype "output"))
      (node (ref "U7B") (pin "4") (pinfunction "RXD_4") (pintype "bidirectional"))
    )
    (net (code "14") (name "CANTX") (class "Default")
      (node (ref "U$1") (pin "PB9") (pinfunction "PB9_PB9") (pintype "bidirectional"))
      (node (ref "U7") (pin "1") (pinfunction "TXD_1") (pintype "input"))
      (node (ref "U7B") (pin "1") (pinfunction "TXD_1") (pintype "bidirectional"))
    )
    (net (code "15") (name "E_CS") (class "Default")
      (node (ref "JP9") (pin "4") (pinfunction "4_4") (pintype "passive"))
      (node (ref "R23") (pin "2") (pinfunction "2_2") (pintype "passive"))
      (node (ref "U$1") (pin "PC10") (pinfunction "PC10_PC10") (pintype "bidirectional"))
    )
    (net (code "16") (name "E_LAT") (class "Default")
      (node (ref "JP10") (pin "1") (pinfunction "1_1") (pintype "passive"))
      (node (ref "R22") (pin "2") (pinfunction "2_2") (pintype "passive"))
      (node (ref "U$1") (pin "PC11") (pinfunction "PC11_PC11") (pintype "bidirectional"))
    )
    (net (code "17") (name "GND") (class "Default")
      (node (ref "C1") (pin "2") (pinfunction "2_2") (pintype "passive"))
      (node (ref "C10") (pin "2") (pinfunction "2_2") (pintype "passive"))
      (node (ref "C11") (pin "2") (pinfunction "2_2") (pintype "passive"))
      (node (ref "C2") (pin "-") (pinfunction "-_-") (pintype "passive"))
      (node (ref "C3") (pin "2") (pinfunction "2_2") (pintype "passive"))
      (node (ref "C4") (pin "2") (pinfunction "2_2") (pintype "passive"))
      (node (ref "C5") (pin "2") (pinfunction "2_2") (pintype "passive"))
      (node (ref "C6") (pin "2") (pinfunction "2_2") (pintype "passive"))
      (node (ref "C7") (pin "2") (pinfunction "2_2") (pintype "passive"))
      (node (ref "C8") (pin "2") (pinfunction "2_2") (pintype "passive"))
      (node (ref "C9") (pin "2") (pinfunction "2_2") (pintype "passive"))
      (node (ref "D1") (pin "A") (pinfunction "A_A") (pintype "passive"))
      (node (ref "IC3") (pin "13") (pinfunction "G_13") (pintype "input"))
      (node (ref "IC3") (pin "8") (pinfunction "GND_8") (pintype "power_in"))
      (node (ref "IC5") (pin "13") (pinfunction "G_13") (pintype "input"))
      (node (ref "IC5") (pin "8") (pinfunction "GND_8") (pintype "power_in"))
      (node (ref "J1") (pin "3") (pinfunction "3_3") (pintype "passive"))
      (node (ref "J1") (pin "6") (pinfunction "6_6") (pintype "passive"))
      (node (ref "J1") (pin "7") (pinfunction "7_7") (pintype "passive"))
      (node (ref "J2") (pin "3") (pinfunction "3_3") (pintype "passive"))
      (node (ref "J2") (pin "6") (pinfunction "6_6") (pintype "passive"))
      (node (ref "J2") (pin "7") (pinfunction "7_7") (pintype "passive"))
      (node (ref "J3") (pin "2") (pinfunction "2_2") (pintype "passive"))
      (node (ref "J3") (pin "3") (pinfunction "3_3") (pintype "passive"))
      (node (ref "JP10") (pin "4") (pinfunction "4_4") (pintype "passive"))
      (node (ref "JP11") (pin "5") (pinfunction "5_5") (pintype "passive"))
      (node (ref "JP11") (pin "6") (pinfunction "6_6") (pintype "passive"))
      (node (ref "JP12") (pin "5") (pinfunction "5_5") (pintype "passive"))
      (node (ref "JP12") (pin "6") (pinfunction "6_6") (pintype "passive"))
      (node (ref "JP16") (pin "5") (pinfunction "5_5") (pintype "passive"))
      (node (ref "JP16") (pin "6") (pinfunction "6_6") (pintype "passive"))
      (node (ref "JP7") (pin "5") (pinfunction "5_5") (pintype "passive"))
      (node (ref "JP7") (pin "6") (pinfunction "6_6") (pintype "passive"))
      (node (ref "JP8") (pin "4") (pinfunction "4_4") (pintype "passive"))
      (node (ref "PORTA") (pin "5") (pinfunction "5_5") (pintype "passive"))
      (node (ref "PORTB") (pin "5") (pinfunction "5_5") (pintype "passive"))
      (node (ref "PORTC") (pin "5") (pinfunction "5_5") (pintype "passive"))
      (node (ref "Q1") (pin "2") (pinfunction "S_2") (pintype "passive"))
      (node (ref "Q10") (pin "2") (pinfunction "S_2") (pintype "passive"))
      (node (ref "Q11") (pin "2") (pinfunction "S_2") (pintype "passive"))
      (node (ref "Q12") (pin "2") (pinfunction "S_2") (pintype "passive"))
      (node (ref "Q13") (pin "2") (pinfunction "S_2") (pintype "passive"))
      (node (ref "Q14") (pin "2") (pinfunction "S_2") (pintype "passive"))
      (node (ref "Q15") (pin "2") (pinfunction "S_2") (pintype "passive"))
      (node (ref "Q16") (pin "2") (pinfunction "S_2") (pintype "passive"))
      (node (ref "Q2") (pin "2") (pinfunction "S_2") (pintype "passive"))
      (node (ref "Q3") (pin "2") (pinfunction "S_2") (pintype "passive"))
      (node (ref "Q4") (pin "2") (pinfunction "S_2") (pintype "passive"))
      (node (ref "Q5") (pin "2") (pinfunction "S_2") (pintype "passive"))
      (node (ref "Q6") (pin "2") (pinfunction "S_2") (pintype "passive"))
      (node (ref "Q7") (pin "2") (pinfunction "S_2") (pintype "passive"))
      (node (ref "Q8") (pin "2") (pinfunction "S_2") (pintype "passive"))
      (node (ref "Q9") (pin "2") (pinfunction "S_2") (pintype "passive"))
      (node (ref "R2") (pin "1") (pinfunction "1_1") (pintype "passive"))
      (node (ref "R61") (pin "2") (pinfunction "2_2") (pintype "passive"))
      (node (ref "SJ12") (pin "P$2") (pinfunction "2_P$2") (pintype "passive"))
      (node (ref "SJ3") (pin "2") (pinfunction "2_2") (pintype "passive"))
      (node (ref "SJ6") (pin "P$2") (pinfunction "2_P$2") (pintype "passive"))
      (node (ref "SJ9") (pin "2") (pinfunction "2_2") (pintype "passive"))
      (node (ref "U$1") (pin "GND3") (pinfunction "GND3_GND3") (pintype "power_in"))
      (node (ref "U$1") (pin "GND5") (pinfunction "GND5_GND5") (pintype "power_in"))
      (node (ref "U$1") (pin "GND6") (pinfunction "GND6_GND6") (pintype "power_in"))
      (node (ref "U$1") (pin "GND7") (pinfunction "GND7_GND7") (pintype "power_in"))
      (node (ref "U$1") (pin "GND8") (pinfunction "GND8_GND8") (pintype "power_in"))
      (node (ref "U1") (pin "6") (pinfunction "INH_6") (pintype "input"))
      (node (ref "U1") (pin "8") (pinfunction "GND_8") (pintype "power_in"))
      (node (ref "U10") (pin "11") (pinfunction "V-_11") (pintype "power_in"))
      (node (ref "U2") (pin "6") (pinfunction "INH_6") (pintype "input"))
      (node (ref "U2") (pin "8") (pinfunction "GND_8") (pintype "power_in"))
      (node (ref "U3") (pin "3") (pinfunction "VSS_3") (pintype "power_in"))
      (node (ref "U4") (pin "3") (pinfunction "VSS_3") (pintype "power_in"))
      (node (ref "U5") (pin "3") (pinfunction "VSS_3") (pintype "power_in"))
      (node (ref "U6") (pin "3") (pinfunction "VSS_3") (pintype "power_in"))
      (node (ref "U7") (pin "2") (pinfunction "GND_2") (pintype "power_in"))
      (node (ref "U7B") (pin "2") (pinfunction "VSS_2") (pintype "power_in"))
      (node (ref "U8") (pin "4") (pinfunction "SD_4") (pintype "bidirectional"))
      (node (ref "U8") (pin "5") (pinfunction "GND1_5") (pintype "power_in"))
      (node (ref "U8") (pin "6") (pinfunction "GND2_6") (pintype "power_in"))
      (node (ref "U8") (pin "7") (pinfunction "GND3_7") (pintype "power_in"))
      (node (ref "U8") (pin "8") (pinfunction "GND4_8") (pintype "power_in"))
      (node (ref "U8B") (pin "2") (pinfunction "GNDSIG_2") (pintype "input"))
      (node (ref "U8B") (pin "3") (pinfunction "~{ON/OFF}_3") (pintype "input"))
      (node (ref "U8B") (pin "4") (pinfunction "GND_4") (pintype "power_in"))
      (node (ref "U9") (pin "11") (pinfunction "V-_11") (pintype "power_in"))
      (node (ref "X1") (pin "2") (pinfunction "2_2") (pintype "passive"))
    )
    (net (code "18") (name "I2CSCL") (class "Default")
      (node (ref "JP8") (pin "2") (pinfunction "2_2") (pintype "passive"))
      (node (ref "R63") (pin "2") (pinfunction "2_2") (pintype "passive"))
      (node (ref "U$1") (pin "PB6") (pinfunction "PB6_PB6") (pintype "bidirectional"))
    )
    (net (code "19") (name "I2CSDA") (class "Default")
      (node (ref "JP8") (pin "1") (pinfunction "1_1") (pintype "passive"))
      (node (ref "R62") (pin "2") (pinfunction "2_2") (pintype "passive"))
      (node (ref "U$1") (pin "PB7") (pinfunction "PB7_PB7") (pintype "bidirectional"))
    )
    (net (code "20") (name "ILAT") (class "Default")
      (node (ref "U$1") (pin "PA6") (pinfunction "PA6_PA6") (pintype "bidirectional"))
      (node (ref "U1") (pin "15") (pinfunction "SH/~{LD}_15") (pintype "input"))
      (node (ref "U2") (pin "15") (pinfunction "SH/~{LD}_15") (pintype "input"))
    )
    (net (code "21") (name "MISO") (class "Default")
      (node (ref "JP9") (pin "1") (pinfunction "1_1") (pintype "passive"))
      (node (ref "U$1") (pin "PB4") (pinfunction "PB4_PB4") (pintype "bidirectional"))
    )
    (net (code "22") (name "MISO2") (class "Default")
      (node (ref "SJ13") (pin "P$2") (pinfunction "2_P$2") (pintype "passive"))
      (node (ref "U$1") (pin "PC2") (pinfunction "PC2_PC2") (pintype "bidirectional"))
      (node (ref "U2") (pin "13") (pinfunction "QH_13") (pintype "output"))
    )
    (net (code "23") (name "MOSI") (class "Default")
      (node (ref "IC5") (pin "14") (pinfunction "SER_14") (pintype "input"))
      (node (ref "R20") (pin "1") (pinfunction "1_1") (pintype "passive"))
      (node (ref "SJ15") (pin "1") (pinfunction "1_1") (pintype "passive"))
      (node (ref "SJ17") (pin "P$2") (pinfunction "2_P$2") (pintype "passive"))
      (node (ref "U$1") (pin "PB5") (pinfunction "PB5_PB5") (pintype "bidirectional"))
    )
    (net (code "24") (name "Net-(D2-PadA)") (class "Default")
      (node (ref "D2") (pin "A") (pinfunction "A_A") (pintype "passive"))
      (node (ref "JP4") (pin "4") (pinfunction "4_4") (pintype "passive"))
    )
    (net (code "25") (name "Net-(D2-PadC)") (class "Default")
      (node (ref "D2") (pin "C") (pinfunction "C_C") (pintype "passive"))
      (node (ref "JP4") (pin "1") (pinfunction "1_1") (pintype "passive"))
    )
    (net (code "26") (name "Net-(IC2-CD+)") (class "Default")
      (node (ref "IC2") (pin "10") (pinfunction "CD+_10") (pintype "passive"))
      (node (ref "SJ4") (pin "P$1") (pinfunction "1_P$1") (pintype "passive"))
      (node (ref "SJ5") (pin "P$1") (pinfunction "1_P$1") (pintype "passive"))
      (node (ref "SJ6") (pin "P$1") (pinfunction "1_P$1") (pintype "passive"))
    )
    (net (code "27") (name "Net-(IC2-GND)") (class "Default")
      (node (ref "IC2") (pin "9") (pinfunction "GND_9") (pintype "power_in"))
      (node (ref "SJ1") (pin "P$1") (pinfunction "1_P$1") (pintype "passive"))
      (node (ref "SJ2") (pin "P$1") (pinfunction "1_P$1") (pintype "passive"))
      (node (ref "SJ3") (pin "1") (pinfunction "1_1") (pintype "passive"))
    )
    (net (code "28") (name "Net-(IC2-I1)") (class "Default")
      (node (ref "IC2") (pin "1") (pinfunction "I1_1") (pintype "input"))
      (node (ref "IC5") (pin "15") (pinfunction "QA_15") (pintype "tri_state"))
      (node (ref "R3") (pin "1") (pinfunction "1_1") (pintype "passive"))
    )
    (net (code "29") (name "Net-(IC2-I2)") (class "Default")
      (node (ref "IC2") (pin "2") (pinfunction "I2_2") (pintype "input"))
      (node (ref "IC5") (pin "1") (pinfunction "QB_1") (pintype "tri_state"))
      (node (ref "R4") (pin "1") (pinfunction "1_1") (pintype "passive"))
    )
    (net (code "30") (name "Net-(IC2-I3)") (class "Default")
      (node (ref "IC2") (pin "3") (pinfunction "I3_3") (pintype "input"))
      (node (ref "IC5") (pin "2") (pinfunction "QC_2") (pintype "tri_state"))
      (node (ref "R5") (pin "1") (pinfunction "1_1") (pintype "passive"))
    )
    (net (code "31") (name "Net-(IC2-I4)") (class "Default")
      (node (ref "IC2") (pin "4") (pinfunction "I4_4") (pintype "input"))
      (node (ref "IC5") (pin "3") (pinfunction "QD_3") (pintype "tri_state"))
      (node (ref "R6") (pin "1") (pinfunction "1_1") (pintype "passive"))
    )
    (net (code "32") (name "Net-(IC2-I5)") (class "Default")
      (node (ref "IC2") (pin "5") (pinfunction "I5_5") (pintype "input"))
      (node (ref "IC5") (pin "4") (pinfunction "QE_4") (pintype "tri_state"))
      (node (ref "R7") (pin "1") (pinfunction "1_1") (pintype "passive"))
    )
    (net (code "33") (name "Net-(IC2-I6)") (class "Default")
      (node (ref "IC2") (pin "6") (pinfunction "I6_6") (pintype "input"))
      (node (ref "IC5") (pin "5") (pinfunction "QF_5") (pintype "tri_state"))
      (node (ref "R8") (pin "1") (pinfunction "1_1") (pintype "passive"))
    )
    (net (code "34") (name "Net-(IC2-I7)") (class "Default")
      (node (ref "IC2") (pin "7") (pinfunction "I7_7") (pintype "input"))
      (node (ref "IC5") (pin "6") (pinfunction "QG_6") (pintype "tri_state"))
      (node (ref "R9") (pin "1") (pinfunction "1_1") (pintype "passive"))
    )
    (net (code "35") (name "Net-(IC2-I8)") (class "Default")
      (node (ref "IC2") (pin "8") (pinfunction "I8_8") (pintype "input"))
      (node (ref "IC5") (pin "7") (pinfunction "QH_7") (pintype "tri_state"))
      (node (ref "R10") (pin "1") (pinfunction "1_1") (pintype "passive"))
    )
    (net (code "36") (name "Net-(IC2-O1)") (class "Default")
      (node (ref "IC2") (pin "18") (pinfunction "O1_18") (pintype "open_collector"))
      (node (ref "JP1") (pin "1") (pinfunction "1_1") (pintype "passive"))
      (node (ref "Q1") (pin "3") (pinfunction "D_3") (pintype "passive"))
    )
    (net (code "37") (name "Net-(IC2-O2)") (class "Default")
      (node (ref "IC2") (pin "17") (pinfunction "O2_17") (pintype "open_collector"))
      (node (ref "JP1") (pin "2") (pinfunction "2_2") (pintype "passive"))
      (node (ref "Q2") (pin "3") (pinfunction "D_3") (pintype "passive"))
    )
    (net (code "38") (name "Net-(IC2-O3)") (class "Default")
      (node (ref "IC2") (pin "16") (pinfunction "O3_16") (pintype "open_collector"))
      (node (ref "JP1") (pin "3") (pinfunction "3_3") (pintype "passive"))
      (node (ref "Q3") (pin "3") (pinfunction "D_3") (pintype "passive"))
    )
    (net (code "39") (name "Net-(IC2-O4)") (class "Default")
      (node (ref "IC2") (pin "15") (pinfunction "O4_15") (pintype "open_collector"))
      (node (ref "JP1") (pin "4") (pinfunction "4_4") (pintype "passive"))
      (node (ref "Q4") (pin "3") (pinfunction "D_3") (pintype "passive"))
    )
    (net (code "40") (name "Net-(IC2-O5)") (class "Default")
      (node (ref "IC2") (pin "14") (pinfunction "O5_14") (pintype "open_collector"))
      (node (ref "JP1") (pin "5") (pinfunction "5_5") (pintype "passive"))
      (node (ref "Q5") (pin "3") (pinfunction "D_3") (pintype "passive"))
    )
    (net (code "41") (name "Net-(IC2-O6)") (class "Default")
      (node (ref "IC2") (pin "13") (pinfunction "O6_13") (pintype "open_collector"))
      (node (ref "JP1") (pin "6") (pinfunction "6_6") (pintype "passive"))
      (node (ref "Q6") (pin "3") (pinfunction "D_3") (pintype "passive"))
    )
    (net (code "42") (name "Net-(IC2-O7)") (class "Default")
      (node (ref "IC2") (pin "12") (pinfunction "O7_12") (pintype "open_collector"))
      (node (ref "JP1") (pin "7") (pinfunction "7_7") (pintype "passive"))
      (node (ref "Q7") (pin "3") (pinfunction "D_3") (pintype "passive"))
    )
    (net (code "43") (name "Net-(IC2-O8)") (class "Default")
      (node (ref "IC2") (pin "11") (pinfunction "O8_11") (pintype "open_collector"))
      (node (ref "JP1") (pin "8") (pinfunction "8_8") (pintype "passive"))
      (node (ref "Q8") (pin "3") (pinfunction "D_3") (pintype "passive"))
    )
    (net (code "44") (name "Net-(IC3A-QA)") (class "Default")
      (node (ref "IC3") (pin "15") (pinfunction "QA_15") (pintype "tri_state"))
      (node (ref "IC8") (pin "1") (pinfunction "I1_1") (pintype "input"))
      (node (ref "R11") (pin "1") (pinfunction "1_1") (pintype "passive"))
    )
    (net (code "45") (name "Net-(IC3A-QB)") (class "Default")
      (node (ref "IC3") (pin "1") (pinfunction "QB_1") (pintype "tri_state"))
      (node (ref "IC8") (pin "2") (pinfunction "I2_2") (pintype "input"))
      (node (ref "R12") (pin "1") (pinfunction "1_1") (pintype "passive"))
    )
    (net (code "46") (name "Net-(IC3A-QC)") (class "Default")
      (node (ref "IC3") (pin "2") (pinfunction "QC_2") (pintype "tri_state"))
      (node (ref "IC8") (pin "3") (pinfunction "I3_3") (pintype "input"))
      (node (ref "R13") (pin "1") (pinfunction "1_1") (pintype "passive"))
    )
    (net (code "47") (name "Net-(IC3A-QD)") (class "Default")
      (node (ref "IC3") (pin "3") (pinfunction "QD_3") (pintype "tri_state"))
      (node (ref "IC8") (pin "4") (pinfunction "I4_4") (pintype "input"))
      (node (ref "R14") (pin "1") (pinfunction "1_1") (pintype "passive"))
    )
    (net (code "48") (name "Net-(IC3A-QE)") (class "Default")
      (node (ref "IC3") (pin "4") (pinfunction "QE_4") (pintype "tri_state"))
      (node (ref "IC8") (pin "5") (pinfunction "I5_5") (pintype "input"))
      (node (ref "R15") (pin "1") (pinfunction "1_1") (pintype "passive"))
    )
    (net (code "49") (name "Net-(IC3A-QF)") (class "Default")
      (node (ref "IC3") (pin "5") (pinfunction "QF_5") (pintype "tri_state"))
      (node (ref "IC8") (pin "6") (pinfunction "I6_6") (pintype "input"))
      (node (ref "R16") (pin "1") (pinfunction "1_1") (pintype "passive"))
    )
    (net (code "50") (name "Net-(IC3A-QG)") (class "Default")
      (node (ref "IC3") (pin "6") (pinfunction "QG_6") (pintype "tri_state"))
      (node (ref "IC8") (pin "7") (pinfunction "I7_7") (pintype "input"))
      (node (ref "R17") (pin "1") (pinfunction "1_1") (pintype "passive"))
    )
    (net (code "51") (name "Net-(IC3A-QH)") (class "Default")
      (node (ref "IC3") (pin "7") (pinfunction "QH_7") (pintype "tri_state"))
      (node (ref "IC8") (pin "8") (pinfunction "I8_8") (pintype "input"))
      (node (ref "R18") (pin "1") (pinfunction "1_1") (pintype "passive"))
    )
    (net (code "52") (name "Net-(IC8-CD+)") (class "Default")
      (node (ref "IC8") (pin "10") (pinfunction "CD+_10") (pintype "passive"))
      (node (ref "SJ10") (pin "P$1") (pinfunction "1_P$1") (pintype "passive"))
      (node (ref "SJ11") (pin "P$1") (pinfunction "1_P$1") (pintype "passive"))
      (node (ref "SJ12") (pin "P$1") (pinfunction "1_P$1") (pintype "passive"))
    )
    (net (code "53") (name "Net-(IC8-GND)") (class "Default")
      (node (ref "IC8") (pin "9") (pinfunction "GND_9") (pintype "power_in"))
      (node (ref "SJ7") (pin "P$1") (pinfunction "1_P$1") (pintype "passive"))
      (node (ref "SJ8") (pin "P$1") (pinfunction "1_P$1") (pintype "passive"))
      (node (ref "SJ9") (pin "1") (pinfunction "1_1") (pintype "passive"))
    )
    (net (code "54") (name "Net-(IC8-O1)") (class "Default")
      (node (ref "IC8") (pin "18") (pinfunction "O1_18") (pintype "open_collector"))
      (node (ref "JP6") (pin "1") (pinfunction "1_1") (pintype "passive"))
      (node (ref "Q9") (pin "3") (pinfunction "D_3") (pintype "passive"))
    )
    (net (code "55") (name "Net-(IC8-O2)") (class "Default")
      (node (ref "IC8") (pin "17") (pinfunction "O2_17") (pintype "open_collector"))
      (node (ref "JP6") (pin "2") (pinfunction "2_2") (pintype "passive"))
      (node (ref "Q10") (pin "3") (pinfunction "D_3") (pintype "passive"))
    )
    (net (code "56") (name "Net-(IC8-O3)") (class "Default")
      (node (ref "IC8") (pin "16") (pinfunction "O3_16") (pintype "open_collector"))
      (node (ref "JP6") (pin "3") (pinfunction "3_3") (pintype "passive"))
      (node (ref "Q11") (pin "3") (pinfunction "D_3") (pintype "passive"))
    )
    (net (code "57") (name "Net-(IC8-O4)") (class "Default")
      (node (ref "IC8") (pin "15") (pinfunction "O4_15") (pintype "open_collector"))
      (node (ref "JP6") (pin "4") (pinfunction "4_4") (pintype "passive"))
      (node (ref "Q12") (pin "3") (pinfunction "D_3") (pintype "passive"))
    )
    (net (code "58") (name "Net-(IC8-O5)") (class "Default")
      (node (ref "IC8") (pin "14") (pinfunction "O5_14") (pintype "open_collector"))
      (node (ref "JP6") (pin "5") (pinfunction "5_5") (pintype "passive"))
      (node (ref "Q13") (pin "3") (pinfunction "D_3") (pintype "passive"))
    )
    (net (code "59") (name "Net-(IC8-O6)") (class "Default")
      (node (ref "IC8") (pin "13") (pinfunction "O6_13") (pintype "open_collector"))
      (node (ref "JP6") (pin "6") (pinfunction "6_6") (pintype "passive"))
      (node (ref "Q14") (pin "3") (pinfunction "D_3") (pintype "passive"))
    )
    (net (code "60") (name "Net-(IC8-O7)") (class "Default")
      (node (ref "IC8") (pin "12") (pinfunction "O7_12") (pintype "open_collector"))
      (node (ref "JP6") (pin "7") (pinfunction "7_7") (pintype "passive"))
      (node (ref "Q15") (pin "3") (pinfunction "D_3") (pintype "passive"))
    )
    (net (code "61") (name "Net-(IC8-O8)") (class "Default")
      (node (ref "IC8") (pin "11") (pinfunction "O8_11") (pintype "open_collector"))
      (node (ref "JP6") (pin "8") (pinfunction "8_8") (pintype "passive"))
      (node (ref "Q16") (pin "3") (pinfunction "D_3") (pintype "passive"))
    )
    (net (code "62") (name "Net-(J1-Pad4)") (class "Default")
      (node (ref "J1") (pin "4") (pinfunction "4_4") (pintype "passive"))
      (node (ref "J2") (pin "4") (pinfunction "4_4") (pintype "passive"))
    )
    (net (code "63") (name "Net-(J1-Pad5)") (class "Default")
      (node (ref "J1") (pin "5") (pinfunction "5_5") (pintype "passive"))
      (node (ref "J2") (pin "5") (pinfunction "5_5") (pintype "passive"))
    )
    (net (code "64") (name "Net-(JP2-Pad1)") (class "Default")
      (node (ref "JP2") (pin "1") (pinfunction "1_1") (pintype "passive"))
      (node (ref "PORTB") (pin "1") (pinfunction "1_1") (pintype "passive"))
      (node (ref "R35") (pin "2") (pinfunction "2_2") (pintype "passive"))
      (node (ref "R45") (pin "2") (pinfunction "2_2") (pintype "passive"))
      (node (ref "RN1") (pin "1") (pinfunction "1_1") (pintype "passive"))
      (node (ref "RN2") (pin "9") (pinfunction "9_9") (pintype "passive"))
    )
    (net (code "65") (name "Net-(JP3-Pad1)") (class "Default")
      (node (ref "JP3") (pin "1") (pinfunction "1_1") (pintype "passive"))
      (node (ref "PORTA") (pin "1") (pinfunction "1_1") (pintype "passive"))
      (node (ref "R44") (pin "2") (pinfunction "2_2") (pintype "passive"))
      (node (ref "R53") (pin "2") (pinfunction "2_2") (pintype "passive"))
      (node (ref "RN3") (pin "1") (pinfunction "1_1") (pintype "passive"))
      (node (ref "RN4") (pin "9") (pinfunction "9_9") (pintype "passive"))
    )
    (net (code "66") (name "Net-(JP4-Pad3)") (class "Default")
      (node (ref "JP4") (pin "3") (pinfunction "3_3") (pintype "passive"))
      (node (ref "R40") (pin "2") (pinfunction "2_2") (pintype "passive"))
    )
    (net (code "67") (name "Net-(Q1-G)") (class "Default")
      (node (ref "Q1") (pin "1") (pinfunction "G_1") (pintype "passive"))
      (node (ref "R3") (pin "2") (pinfunction "2_2") (pintype "passive"))
    )
    (net (code "68") (name "Net-(Q2-G)") (class "Default")
      (node (ref "Q2") (pin "1") (pinfunction "G_1") (pintype "passive"))
      (node (ref "R4") (pin "2") (pinfunction "2_2") (pintype "passive"))
    )
    (net (code "69") (name "Net-(Q3-G)") (class "Default")
      (node (ref "Q3") (pin "1") (pinfunction "G_1") (pintype "passive"))
      (node (ref "R5") (pin "2") (pinfunction "2_2") (pintype "passive"))
    )
    (net (code "70") (name "Net-(Q4-G)") (class "Default")
      (node (ref "Q4") (pin "1") (pinfunction "G_1") (pintype "passive"))
      (node (ref "R6") (pin "2") (pinfunction "2_2") (pintype "passive"))
    )
    (net (code "71") (name "Net-(Q5-G)") (class "Default")
      (node (ref "Q5") (pin "1") (pinfunction "G_1") (pintype "passive"))
      (node (ref "R7") (pin "2") (pinfunction "2_2") (pintype "passive"))
    )
    (net (code "72") (name "Net-(Q6-G)") (class "Default")
      (node (ref "Q6") (pin "1") (pinfunction "G_1") (pintype "passive"))
      (node (ref "R8") (pin "2") (pinfunction "2_2") (pintype "passive"))
    )
    (net (code "73") (name "Net-(Q7-G)") (class "Default")
      (node (ref "Q7") (pin "1") (pinfunction "G_1") (pintype "passive"))
      (node (ref "R9") (pin "2") (pinfunction "2_2") (pintype "passive"))
    )
    (net (code "74") (name "Net-(Q8-G)") (class "Default")
      (node (ref "Q8") (pin "1") (pinfunction "G_1") (pintype "passive"))
      (node (ref "R10") (pin "2") (pinfunction "2_2") (pintype "passive"))
    )
    (net (code "75") (name "Net-(Q9-G)") (class "Default")
      (node (ref "Q9") (pin "1") (pinfunction "G_1") (pintype "passive"))
      (node (ref "R11") (pin "2") (pinfunction "2_2") (pintype "passive"))
    )
    (net (code "76") (name "Net-(Q10-G)") (class "Default")
      (node (ref "Q10") (pin "1") (pinfunction "G_1") (pintype "passive"))
      (node (ref "R12") (pin "2") (pinfunction "2_2") (pintype "passive"))
    )
    (net (code "77") (name "Net-(Q11-G)") (class "Default")
      (node (ref "Q11") (pin "1") (pinfunction "G_1") (pintype "passive"))
      (node (ref "R13") (pin "2") (pinfunction "2_2") (pintype "passive"))
    )
    (net (code "78") (name "Net-(Q12-G)") (class "Default")
      (node (ref "Q12") (pin "1") (pinfunction "G_1") (pintype "passive"))
      (node (ref "R14") (pin "2") (pinfunction "2_2") (pintype "passive"))
    )
    (net (code "79") (name "Net-(Q13-G)") (class "Default")
      (node (ref "Q13") (pin "1") (pinfunction "G_1") (pintype "passive"))
      (node (ref "R15") (pin "2") (pinfunction "2_2") (pintype "passive"))
    )
    (net (code "80") (name "Net-(Q14-G)") (class "Default")
      (node (ref "Q14") (pin "1") (pinfunction "G_1") (pintype "passive"))
      (node (ref "R16") (pin "2") (pinfunction "2_2") (pintype "passive"))
    )
    (net (code "81") (name "Net-(Q15-G)") (class "Default")
      (node (ref "Q15") (pin "1") (pinfunction "G_1") (pintype "passive"))
      (node (ref "R17") (pin "2") (pinfunction "2_2") (pintype "passive"))
    )
    (net (code "82") (name "Net-(Q16-G)") (class "Default")
      (node (ref "Q16") (pin "1") (pinfunction "G_1") (pintype "passive"))
      (node (ref "R18") (pin "2") (pinfunction "2_2") (pintype "passive"))
    )
    (net (code "83") (name "Net-(RN1A-2)") (class "Default")
      (node (ref "R35") (pin "1") (pinfunction "1_1") (pintype "passive"))
      (node (ref "RN1") (pin "16") (pinfunction "2_16") (pintype "passive"))
      (node (ref "U2") (pin "14") (pinfunction "H_14") (pintype "input"))
    )
    (net (code "84") (name "Net-(RN1B-1)") (class "Default")
      (node (ref "JP2") (pin "2") (pinfunction "2_2") (pintype "passive"))
      (node (ref "PORTB") (pin "2") (pinfunction "2_2") (pintype "passive"))
      (node (ref "R34") (pin "2") (pinfunction "2_2") (pintype "passive"))
      (node (ref "R46") (pin "1") (pinfunction "1_1") (pintype "passive"))
      (node (ref "RN1") (pin "2") (pinfunction "1_2") (pintype "passive"))
      (node (ref "RN2") (pin "8") (pinfunction "8_8") (pintype "passive"))
    )
    (net (code "85") (name "Net-(RN1B-2)") (class "Default")
      (node (ref "R34") (pin "1") (pinfunction "1_1") (pintype "passive"))
      (node (ref "RN1") (pin "15") (pinfunction "2_15") (pintype "passive"))
      (node (ref "U2") (pin "12") (pinfunction "G_12") (pintype "input"))
    )
    (net (code "86") (name "Net-(RN1C-1)") (class "Default")
      (node (ref "JP2") (pin "3") (pinfunction "3_3") (pintype "passive"))
      (node (ref "PORTB") (pin "3") (pinfunction "3_3") (pintype "passive"))
      (node (ref "R33") (pin "2") (pinfunction "2_2") (pintype "passive"))
      (node (ref "R47") (pin "1") (pinfunction "1_1") (pintype "passive"))
      (node (ref "RN1") (pin "3") (pinfunction "1_3") (pintype "passive"))
      (node (ref "RN2") (pin "7") (pinfunction "7_7") (pintype "passive"))
    )
    (net (code "87") (name "Net-(RN1C-2)") (class "Default")
      (node (ref "R33") (pin "1") (pinfunction "1_1") (pintype "passive"))
      (node (ref "RN1") (pin "14") (pinfunction "2_14") (pintype "passive"))
      (node (ref "U2") (pin "11") (pinfunction "F_11") (pintype "input"))
    )
    (net (code "88") (name "Net-(RN1D-1)") (class "Default")
      (node (ref "JP2") (pin "4") (pinfunction "4_4") (pintype "passive"))
      (node (ref "PORTB") (pin "4") (pinfunction "4_4") (pintype "passive"))
      (node (ref "R32") (pin "2") (pinfunction "2_2") (pintype "passive"))
      (node (ref "R48") (pin "1") (pinfunction "1_1") (pintype "passive"))
      (node (ref "RN1") (pin "4") (pinfunction "1_4") (pintype "passive"))
      (node (ref "RN2") (pin "6") (pinfunction "6_6") (pintype "passive"))
    )
    (net (code "89") (name "Net-(RN1D-2)") (class "Default")
      (node (ref "R32") (pin "1") (pinfunction "1_1") (pintype "passive"))
      (node (ref "RN1") (pin "13") (pinfunction "2_13") (pintype "passive"))
      (node (ref "U2") (pin "10") (pinfunction "E_10") (pintype "input"))
    )
    (net (code "90") (name "Net-(RN1E-1)") (class "Default")
      (node (ref "JP2") (pin "5") (pinfunction "5_5") (pintype "passive"))
      (node (ref "PORTB") (pin "7") (pinfunction "7_7") (pintype "passive"))
      (node (ref "R31") (pin "2") (pinfunction "2_2") (pintype "passive"))
      (node (ref "R49") (pin "1") (pinfunction "1_1") (pintype "passive"))
      (node (ref "RN1") (pin "5") (pinfunction "1_5") (pintype "passive"))
      (node (ref "RN2") (pin "5") (pinfunction "5_5") (pintype "passive"))
    )
    (net (code "91") (name "Net-(RN1E-2)") (class "Default")
      (node (ref "R31") (pin "1") (pinfunction "1_1") (pintype "passive"))
      (node (ref "RN1") (pin "12") (pinfunction "2_12") (pintype "passive"))
      (node (ref "U2") (pin "5") (pinfunction "D_5") (pintype "input"))
    )
    (net (code "92") (name "Net-(RN1F-1)") (class "Default")
      (node (ref "JP2") (pin "6") (pinfunction "6_6") (pintype "passive"))
      (node (ref "PORTB") (pin "8") (pinfunction "8_8") (pintype "passive"))
      (node (ref "R30") (pin "2") (pinfunction "2_2") (pintype "passive"))
      (node (ref "R50") (pin "1") (pinfunction "1_1") (pintype "passive"))
      (node (ref "RN1") (pin "6") (pinfunction "1_6") (pintype "passive"))
      (node (ref "RN2") (pin "4") (pinfunction "4_4") (pintype "passive"))
    )
    (net (code "93") (name "Net-(RN1F-2)") (class "Default")
      (node (ref "R30") (pin "1") (pinfunction "1_1") (pintype "passive"))
      (node (ref "RN1") (pin "11") (pinfunction "2_11") (pintype "passive"))
      (node (ref "U2") (pin "4") (pinfunction "C_4") (pintype "input"))
    )
    (net (code "94") (name "Net-(RN1G-1)") (class "Default")
      (node (ref "JP2") (pin "7") (pinfunction "7_7") (pintype "passive"))
      (node (ref "PORTB") (pin "9") (pinfunction "9_9") (pintype "passive"))
      (node (ref "R29") (pin "2") (pinfunction "2_2") (pintype "passive"))
      (node (ref "R51") (pin "1") (pinfunction "1_1") (pintype "passive"))
      (node (ref "RN1") (pin "7") (pinfunction "1_7") (pintype "passive"))
      (node (ref "RN2") (pin "3") (pinfunction "3_3") (pintype "passive"))
    )
    (net (code "95") (name "Net-(RN1G-2)") (class "Default")
      (node (ref "R29") (pin "1") (pinfunction "1_1") (pintype "passive"))
      (node (ref "RN1") (pin "10") (pinfunction "2_10") (pintype "passive"))
      (node (ref "U2") (pin "3") (pinfunction "B_3") (pintype "input"))
    )
    (net (code "96") (name "Net-(RN1H-1)") (class "Default")
      (node (ref "JP2") (pin "8") (pinfunction "8_8") (pintype "passive"))
      (node (ref "PORTB") (pin "10") (pinfunction "10_10") (pintype "passive"))
      (node (ref "R28") (pin "2") (pinfunction "2_2") (pintype "passive"))
      (node (ref "R52") (pin "1") (pinfunction "1_1") (pintype "passive"))
      (node (ref "RN1") (pin "8") (pinfunction "1_8") (pintype "passive"))
      (node (ref "RN2") (pin "2") (pinfunction "2_2") (pintype "passive"))
    )
    (net (code "97") (name "Net-(RN1H-2)") (class "Default")
      (node (ref "R28") (pin "1") (pinfunction "1_1") (pintype "passive"))
      (node (ref "RN1") (pin "9") (pinfunction "2_9") (pintype "passive"))
      (node (ref "U2") (pin "2") (pinfunction "A_2") (pintype "input"))
    )
    (net (code "98") (name "Net-(RN3A-2)") (class "Default")
      (node (ref "R44") (pin "1") (pinfunction "1_1") (pintype "passive"))
      (node (ref "RN3") (pin "16") (pinfunction "2_16") (pintype "passive"))
      (node (ref "U1") (pin "14") (pinfunction "H_14") (pintype "input"))
    )
    (net (code "99") (name "Net-(RN3B-1)") (class "Default")
      (node (ref "JP3") (pin "2") (pinfunction "2_2") (pintype "passive"))
      (node (ref "PORTA") (pin "2") (pinfunction "2_2") (pintype "passive"))
      (node (ref "R43") (pin "2") (pinfunction "2_2") (pintype "passive"))
      (node (ref "R54") (pin "2") (pinfunction "2_2") (pintype "passive"))
      (node (ref "RN3") (pin "2") (pinfunction "1_2") (pintype "passive"))
      (node (ref "RN4") (pin "8") (pinfunction "8_8") (pintype "passive"))
    )
    (net (code "100") (name "Net-(RN3B-2)") (class "Default")
      (node (ref "R43") (pin "1") (pinfunction "1_1") (pintype "passive"))
      (node (ref "RN3") (pin "15") (pinfunction "2_15") (pintype "passive"))
      (node (ref "U1") (pin "12") (pinfunction "G_12") (pintype "input"))
    )
    (net (code "101") (name "Net-(RN3C-1)") (class "Default")
      (node (ref "JP3") (pin "3") (pinfunction "3_3") (pintype "passive"))
      (node (ref "PORTA") (pin "3") (pinfunction "3_3") (pintype "passive"))
      (node (ref "R42") (pin "2") (pinfunction "2_2") (pintype "passive"))
      (node (ref "R55") (pin "2") (pinfunction "2_2") (pintype "passive"))
      (node (ref "RN3") (pin "3") (pinfunction "1_3") (pintype "passive"))
      (node (ref "RN4") (pin "7") (pinfunction "7_7") (pintype "passive"))
    )
    (net (code "102") (name "Net-(RN3C-2)") (class "Default")
      (node (ref "R42") (pin "1") (pinfunction "1_1") (pintype "passive"))
      (node (ref "RN3") (pin "14") (pinfunction "2_14") (pintype "passive"))
      (node (ref "U1") (pin "11") (pinfunction "F_11") (pintype "input"))
    )
    (net (code "103") (name "Net-(RN3D-1)") (class "Default")
      (node (ref "JP3") (pin "4") (pinfunction "4_4") (pintype "passive"))
      (node (ref "PORTA") (pin "4") (pinfunction "4_4") (pintype "passive"))
      (node (ref "R41") (pin "2") (pinfunction "2_2") (pintype "passive"))
      (node (ref "R56") (pin "2") (pinfunction "2_2") (pintype "passive"))
      (node (ref "RN3") (pin "4") (pinfunction "1_4") (pintype "passive"))
      (node (ref "RN4") (pin "6") (pinfunction "6_6") (pintype "passive"))
    )
    (net (code "104") (name "Net-(RN3D-2)") (class "Default")
      (node (ref "R41") (pin "1") (pinfunction "1_1") (pintype "passive"))
      (node (ref "RN3") (pin "13") (pinfunction "2_13") (pintype "passive"))
      (node (ref "U1") (pin "10") (pinfunction "E_10") (pintype "input"))
    )
    (net (code "105") (name "Net-(RN3E-1)") (class "Default")
      (node (ref "JP3") (pin "5") (pinfunction "5_5") (pintype "passive"))
      (node (ref "PORTA") (pin "7") (pinfunction "7_7") (pintype "passive"))
      (node (ref "R39") (pin "2") (pinfunction "2_2") (pintype "passive"))
      (node (ref "R57") (pin "2") (pinfunction "2_2") (pintype "passive"))
      (node (ref "RN3") (pin "5") (pinfunction "1_5") (pintype "passive"))
      (node (ref "RN4") (pin "5") (pinfunction "5_5") (pintype "passive"))
    )
    (net (code "106") (name "Net-(RN3E-2)") (class "Default")
      (node (ref "R39") (pin "1") (pinfunction "1_1") (pintype "passive"))
      (node (ref "RN3") (pin "12") (pinfunction "2_12") (pintype "passive"))
      (node (ref "U1") (pin "5") (pinfunction "D_5") (pintype "input"))
    )
    (net (code "107") (name "Net-(RN3F-1)") (class "Default")
      (node (ref "JP3") (pin "6") (pinfunction "6_6") (pintype "passive"))
      (node (ref "PORTA") (pin "8") (pinfunction "8_8") (pintype "passive"))
      (node (ref "R38") (pin "2") (pinfunction "2_2") (pintype "passive"))
      (node (ref "R58") (pin "2") (pinfunction "2_2") (pintype "passive"))
      (node (ref "RN3") (pin "6") (pinfunction "1_6") (pintype "passive"))
      (node (ref "RN4") (pin "4") (pinfunction "4_4") (pintype "passive"))
    )
    (net (code "108") (name "Net-(RN3F-2)") (class "Default")
      (node (ref "R38") (pin "1") (pinfunction "1_1") (pintype "passive"))
      (node (ref "RN3") (pin "11") (pinfunction "2_11") (pintype "passive"))
      (node (ref "U1") (pin "4") (pinfunction "C_4") (pintype "input"))
    )
    (net (code "109") (name "Net-(RN3G-1)") (class "Default")
      (node (ref "JP3") (pin "7") (pinfunction "7_7") (pintype "passive"))
      (node (ref "PORTA") (pin "9") (pinfunction "9_9") (pintype "passive"))
      (node (ref "R37") (pin "2") (pinfunction "2_2") (pintype "passive"))
      (node (ref "R59") (pin "2") (pinfunction "2_2") (pintype "passive"))
      (node (ref "RN3") (pin "7") (pinfunction "1_7") (pintype "passive"))
      (node (ref "RN4") (pin "3") (pinfunction "3_3") (pintype "passive"))
    )
    (net (code "110") (name "Net-(RN3G-2)") (class "Default")
      (node (ref "R37") (pin "1") (pinfunction "1_1") (pintype "passive"))
      (node (ref "RN3") (pin "10") (pinfunction "2_10") (pintype "passive"))
      (node (ref "U1") (pin "3") (pinfunction "B_3") (pintype "input"))
    )
    (net (code "111") (name "Net-(RN3H-1)") (class "Default")
      (node (ref "JP3") (pin "8") (pinfunction "8_8") (pintype "passive"))
      (node (ref "PORTA") (pin "10") (pinfunction "10_10") (pintype "passive"))
      (node (ref "R36") (pin "2") (pinfunction "2_2") (pintype "passive"))
      (node (ref "R60") (pin "2") (pinfunction "2_2") (pintype "passive"))
      (node (ref "RN3") (pin "8") (pinfunction "1_8") (pintype "passive"))
      (node (ref "RN4") (pin "2") (pinfunction "2_2") (pintype "passive"))
    )
    (net (code "112") (name "Net-(RN3H-2)") (class "Default")
      (node (ref "R36") (pin "1") (pinfunction "1_1") (pintype "passive"))
      (node (ref "RN3") (pin "9") (pinfunction "2_9") (pintype "passive"))
      (node (ref "U1") (pin "2") (pinfunction "A_2") (pintype "input"))
    )
    (net (code "113") (name "Net-(SJ13-1)") (class "Default")
      (node (ref "SJ13") (pin "P$1") (pinfunction "1_P$1") (pintype "passive"))
      (node (ref "U$1") (pin "PB14") (pinfunction "PB14_PB14") (pintype "bidirectional"))
    )
    (net (code "114") (name "Net-(SJ14-1)") (class "Default")
      (node (ref "SJ14") (pin "P$1") (pinfunction "1_P$1") (pintype "passive"))
      (node (ref "U$1") (pin "VIN2") (pinfunction "VIN2_VIN2") (pintype "power_in"))
    )
    (net (code "115") (name "Net-(SJ16-2)") (class "Default")
      (node (ref "JP9") (pin "2") (pinfunction "2_2") (pintype "passive"))
      (node (ref "SJ15") (pin "2") (pinfunction "2_2") (pintype "passive"))
      (node (ref "SJ16") (pin "P$2") (pinfunction "2_P$2") (pintype "passive"))
    )
    (net (code "116") (name "Net-(SJ18-2)") (class "Default")
      (node (ref "SJ18") (pin "P$2") (pinfunction "2_P$2") (pintype "passive"))
      (node (ref "U7") (pin "5") (pinfunction "VREF_5") (pintype "output"))
      (node (ref "U7B") (pin "5") (pinfunction "VREF_5") (pintype "bidirectional"))
    )
    (net (code "117") (name "Net-(U3A-O)") (class "Default")
      (node (ref "JP5") (pin "1") (pinfunction "1_1") (pintype "passive"))
      (node (ref "PORTC") (pin "1") (pinfunction "1_1") (pintype "passive"))
      (node (ref "U3") (pin "7") (pinfunction "O_7") (pintype "output"))
      (node (ref "U9") (pin "7") (pinfunction "OUT_7") (pintype "output"))
    )
    (net (code "118") (name "Net-(U3B-O)") (class "Default")
      (node (ref "JP5") (pin "2") (pinfunction "2_2") (pintype "passive"))
      (node (ref "PORTC") (pin "2") (pinfunction "2_2") (pintype "passive"))
      (node (ref "U3") (pin "5") (pinfunction "O_5") (pintype "output"))
      (node (ref "U9") (pin "8") (pinfunction "OUT_8") (pintype "output"))
    )
    (net (code "119") (name "Net-(U4A-O)") (class "Default")
      (node (ref "JP5") (pin "4") (pinfunction "4_4") (pintype "passive"))
      (node (ref "PORTC") (pin "4") (pinfunction "4_4") (pintype "passive"))
      (node (ref "U4") (pin "7") (pinfunction "O_7") (pintype "output"))
      (node (ref "U9") (pin "14") (pinfunction "OUT_14") (pintype "output"))
    )
    (net (code "120") (name "Net-(U4B-O)") (class "Default")
      (node (ref "JP5") (pin "3") (pinfunction "3_3") (pintype "passive"))
      (node (ref "PORTC") (pin "3") (pinfunction "3_3") (pintype "passive"))
      (node (ref "U4") (pin "5") (pinfunction "O_5") (pintype "output"))
      (node (ref "U9") (pin "1") (pinfunction "OUT_1") (pintype "output"))
    )
    (net (code "121") (name "Net-(U7-RS)") (class "Default")
      (node (ref "R61") (pin "1") (pinfunction "1_1") (pintype "passive"))
      (node (ref "U7") (pin "8") (pinfunction "RS_8") (pintype "input"))
      (node (ref "U7B") (pin "8") (pinfunction "RS_8") (pintype "bidirectional"))
    )
    (net (code "122") (name "Net-(U8-VOUT)") (class "Default")
      (node (ref "D1") (pin "C") (pinfunction "C_C") (pintype "passive"))
      (node (ref "L1") (pin "2") (pinfunction "2_2") (pintype "passive"))
      (node (ref "U8") (pin "2") (pinfunction "VOUT_2") (pintype "bidirectional"))
      (node (ref "U8B") (pin "7") (pinfunction "OUT_7") (pintype "passive"))
    )
    (net (code "123") (name "Net-(U10A--IN)") (class "Default")
      (node (ref "R1") (pin "1") (pinfunction "1_1") (pintype "passive"))
      (node (ref "R2") (pin "2") (pinfunction "2_2") (pintype "passive"))
      (node (ref "U10") (pin "13") (pinfunction "-IN_13") (pintype "input"))
      (node (ref "U10") (pin "2") (pinfunction "-IN_2") (pintype "input"))
      (node (ref "U10") (pin "6") (pinfunction "-IN_6") (pintype "input"))
      (node (ref "U10") (pin "9") (pinfunction "-IN_9") (pintype "input"))
      (node (ref "U9") (pin "13") (pinfunction "-IN_13") (pintype "input"))
      (node (ref "U9") (pin "2") (pinfunction "-IN_2") (pintype "input"))
      (node (ref "U9") (pin "6") (pinfunction "-IN_6") (pintype "input"))
      (node (ref "U9") (pin "9") (pinfunction "-IN_9") (pintype "input"))
    )
    (net (code "124") (name "Net-(U10A-OUT)") (class "Default")
      (node (ref "JP5") (pin "7") (pinfunction "7_7") (pintype "passive"))
      (node (ref "PORTC") (pin "9") (pinfunction "9_9") (pintype "passive"))
      (node (ref "U10") (pin "1") (pinfunction "OUT_1") (pintype "output"))
      (node (ref "U6") (pin "5") (pinfunction "O_5") (pintype "output"))
    )
    (net (code "125") (name "Net-(U10B-OUT)") (class "Default")
      (node (ref "JP5") (pin "5") (pinfunction "5_5") (pintype "passive"))
      (node (ref "PORTC") (pin "7") (pinfunction "7_7") (pintype "passive"))
      (node (ref "U10") (pin "7") (pinfunction "OUT_7") (pintype "output"))
      (node (ref "U5") (pin "7") (pinfunction "O_7") (pintype "output"))
    )
    (net (code "126") (name "Net-(U10C-OUT)") (class "Default")
      (node (ref "JP5") (pin "6") (pinfunction "6_6") (pintype "passive"))
      (node (ref "PORTC") (pin "8") (pinfunction "8_8") (pintype "passive"))
      (node (ref "U10") (pin "8") (pinfunction "OUT_8") (pintype "output"))
      (node (ref "U5") (pin "5") (pinfunction "O_5") (pintype "output"))
    )
    (net (code "127") (name "Net-(U10D-OUT)") (class "Default")
      (node (ref "JP5") (pin "8") (pinfunction "8_8") (pintype "passive"))
      (node (ref "PORTC") (pin "10") (pinfunction "10_10") (pintype "passive"))
      (node (ref "U10") (pin "14") (pinfunction "OUT_14") (pintype "output"))
      (node (ref "U6") (pin "7") (pinfunction "O_7") (pintype "output"))
    )
    (net (code "128") (name "OLAT") (class "Default")
      (node (ref "IC3") (pin "12") (pinfunction "RCK_12") (pintype "input"))
      (node (ref "IC5") (pin "12") (pinfunction "RCK_12") (pintype "input"))
      (node (ref "R21") (pin "1") (pinfunction "1_1") (pintype "passive"))
      (node (ref "U$1") (pin "PA8") (pinfunction "PA8_PA8") (pintype "bidirectional"))
    )
    (net (code "129") (name "SCK") (class "Default")
      (node (ref "IC3") (pin "11") (pinfunction "SCK_11") (pintype "input"))
      (node (ref "IC5") (pin "11") (pinfunction "SCK_11") (pintype "input"))
      (node (ref "JP9") (pin "3") (pinfunction "3_3") (pintype "passive"))
      (node (ref "R19") (pin "1") (pinfunction "1_1") (pintype "passive"))
      (node (ref "U$1") (pin "PB3") (pinfunction "PB3_PB3") (pintype "bidirectional"))
    )
    (net (code "130") (name "SCK2") (class "Default")
      (node (ref "U$1") (pin "PB10") (pinfunction "PB10_PB10") (pintype "bidirectional"))
      (node (ref "U1") (pin "7") (pinfunction "CLK_7") (pintype "input"))
      (node (ref "U2") (pin "7") (pinfunction "CLK_7") (pintype "input"))
    )
    (net (code "131") (name "SLNK1") (class "Default")
      (node (ref "IC3") (pin "14") (pinfunction "SER_14") (pintype "input"))
      (node (ref "IC5") (pin "9") (pinfunction "QH*_9") (pintype "tri_state"))
      (node (ref "SJ17") (pin "P$1") (pinfunction "1_P$1") (pintype "passive"))
    )
    (net (code "132") (name "SLNK2") (class "Default")
      (node (ref "IC3") (pin "9") (pinfunction "QH*_9") (pintype "tri_state"))
      (node (ref "SJ16") (pin "P$1") (pinfunction "1_P$1") (pintype "passive"))
    )
    (net (code "133") (name "SLNK3") (class "Default")
      (node (ref "U1") (pin "13") (pinfunction "QH_13") (pintype "output"))
      (node (ref "U2") (pin "1") (pinfunction "SER_1") (pintype "input"))
    )
    (net (code "134") (name "SRV1") (class "Default")
      (node (ref "JP7") (pin "2") (pinfunction "2_2") (pintype "passive"))
      (node (ref "R25") (pin "2") (pinfunction "2_2") (pintype "passive"))
      (node (ref "U$1") (pin "PC9") (pinfunction "PC9_PC9") (pintype "bidirectional"))
    )
    (net (code "135") (name "SRV2") (class "Default")
      (node (ref "JP7") (pin "1") (pinfunction "1_1") (pintype "passive"))
      (node (ref "R24") (pin "2") (pinfunction "2_2") (pintype "passive"))
      (node (ref "U$1") (pin "PC7") (pinfunction "PC7_PC7") (pintype "bidirectional"))
    )
    (net (code "136") (name "SRV3") (class "Default")
      (node (ref "JP11") (pin "2") (pinfunction "2_2") (pintype "passive"))
      (node (ref "R26") (pin "2") (pinfunction "2_2") (pintype "passive"))
      (node (ref "U$1") (pin "PC8") (pinfunction "PC8_PC8") (pintype "bidirectional"))
    )
    (net (code "137") (name "SRV4") (class "Default")
      (node (ref "JP11") (pin "1") (pinfunction "1_1") (pintype "passive"))
      (node (ref "R27") (pin "2") (pinfunction "2_2") (pintype "passive"))
      (node (ref "U$1") (pin "PC6") (pinfunction "PC6_PC6") (pintype "bidirectional"))
    )
    (net (code "138") (name "SRV5") (class "Default")
      (node (ref "JP12") (pin "2") (pinfunction "2_2") (pintype "passive"))
      (node (ref "R64") (pin "2") (pinfunction "2_2") (pintype "passive"))
      (node (ref "U$1") (pin "PF1-PH1") (pinfunction "PF1-PH1_PF1-PH1") (pintype "bidirectional"))
    )
    (net (code "139") (name "SRV6") (class "Default")
      (node (ref "JP12") (pin "1") (pinfunction "1_1") (pintype "passive"))
      (node (ref "R65") (pin "2") (pinfunction "2_2") (pintype "passive"))
      (node (ref "U$1") (pin "PA15") (pinfunction "PA15_PA15") (pintype "bidirectional"))
    )
    (net (code "140") (name "SRV7") (class "Default")
      (node (ref "JP16") (pin "2") (pinfunction "2_2") (pintype "passive"))
      (node (ref "R66") (pin "2") (pinfunction "2_2") (pintype "passive"))
      (node (ref "U$1") (pin "PC12") (pinfunction "PC12_PC12") (pintype "bidirectional"))
    )
    (net (code "141") (name "SRV8") (class "Default")
      (node (ref "JP16") (pin "1") (pinfunction "1_1") (pintype "passive"))
      (node (ref "R67") (pin "2") (pinfunction "2_2") (pintype "passive"))
      (node (ref "U$1") (pin "PD2") (pinfunction "PD2_PD2") (pintype "bidirectional"))
    )
    (net (code "142") (name "TIN1") (class "Default")
      (node (ref "U$1") (pin "PC0") (pinfunction "PC0_PC0") (pintype "bidirectional"))
      (node (ref "U3") (pin "2") (pinfunction "I_2") (pintype "input"))
      (node (ref "U9") (pin "5") (pinfunction "+IN_5") (pintype "input"))
    )
    (net (code "143") (name "TIN2") (class "Default")
      (node (ref "U$1") (pin "PC3") (pinfunction "PC3_PC3") (pintype "bidirectional"))
      (node (ref "U3") (pin "4") (pinfunction "I_4") (pintype "input"))
      (node (ref "U9") (pin "10") (pinfunction "+IN_10") (pintype "input"))
    )
    (net (code "144") (name "TIN3") (class "Default")
      (node (ref "U$1") (pin "PA4") (pinfunction "PA4_PA4") (pintype "bidirectional"))
      (node (ref "U4") (pin "4") (pinfunction "I_4") (pintype "input"))
      (node (ref "U9") (pin "3") (pinfunction "+IN_3") (pintype "input"))
    )
    (net (code "145") (name "TIN4") (class "Default")
      (node (ref "U$1") (pin "PA0") (pinfunction "PA0_PA0") (pintype "bidirectional"))
      (node (ref "U4") (pin "2") (pinfunction "I_2") (pintype "input"))
      (node (ref "U9") (pin "12") (pinfunction "+IN_12") (pintype "input"))
    )
    (net (code "146") (name "TIN5") (class "Default")
      (node (ref "U$1") (pin "PB1") (pinfunction "PB1_PB1") (pintype "bidirectional"))
      (node (ref "U10") (pin "5") (pinfunction "+IN_5") (pintype "input"))
      (node (ref "U5") (pin "2") (pinfunction "I_2") (pintype "input"))
    )
    (net (code "147") (name "TIN6") (class "Default")
      (node (ref "U$1") (pin "PB15") (pinfunction "PB15_PB15") (pintype "bidirectional"))
      (node (ref "U10") (pin "10") (pinfunction "+IN_10") (pintype "input"))
      (node (ref "U5") (pin "4") (pinfunction "I_4") (pintype "input"))
    )
    (net (code "148") (name "TIN7") (class "Default")
      (node (ref "U$1") (pin "PB2") (pinfunction "PB2_PB2") (pintype "bidirectional"))
      (node (ref "U10") (pin "3") (pinfunction "+IN_3") (pintype "input"))
      (node (ref "U6") (pin "4") (pinfunction "I_4") (pintype "input"))
    )
    (net (code "149") (name "TIN8") (class "Default")
      (node (ref "U$1") (pin "PB12") (pinfunction "PB12_PB12") (pintype "bidirectional"))
      (node (ref "U10") (pin "12") (pinfunction "+IN_12") (pintype "input"))
      (node (ref "U6") (pin "2") (pinfunction "I_2") (pintype "input"))
    )
    (net (code "150") (name "V+") (class "Default")
      (node (ref "C1") (pin "1") (pinfunction "1_1") (pintype "passive"))
      (node (ref "C2") (pin "+") (pinfunction "+_+") (pintype "passive"))
      (node (ref "L1") (pin "1") (pinfunction "1_1") (pintype "passive"))
      (node (ref "U$1") (pin "E5V") (pinfunction "E5V_E5V") (pintype "power_in"))
      (node (ref "U8") (pin "3") (pinfunction "FB_3") (pintype "bidirectional"))
      (node (ref "U8B") (pin "1") (pinfunction "FB_1") (pintype "input"))
    )
    (net (code "151") (name "unconnected-(H1-MOUNT-PadB3,3)") (class "Default")
      (node (ref "H1") (pin "B3,3") (pinfunction "MOUNT_B3,3") (pintype "passive"))
    )
    (net (code "152") (name "unconnected-(H2-MOUNT-PadB3,3)") (class "Default")
      (node (ref "H2") (pin "B3,3") (pinfunction "MOUNT_B3,3") (pintype "passive"))
    )
    (net (code "153") (name "unconnected-(H3-MOUNT-PadB3,3)") (class "Default")
      (node (ref "H3") (pin "B3,3") (pinfunction "MOUNT_B3,3") (pintype "passive"))
    )
    (net (code "154") (name "unconnected-(H4-MOUNT-PadB3,3)") (class "Default")
      (node (ref "H4") (pin "B3,3") (pinfunction "MOUNT_B3,3") (pintype "passive"))
    )
    (net (code "155") (name "unconnected-(U$1-PadBOOT0)") (class "Default")
      (node (ref "U$1") (pin "BOOT0") (pinfunction "BOOT0_BOOT0") (pintype "bidirectional"))
    )
    (net (code "156") (name "unconnected-(U$1-PadIOREF2)") (class "Default")
      (node (ref "U$1") (pin "IOREF2") (pinfunction "IOREF2_IOREF2") (pintype "input"))
    )
    (net (code "157") (name "unconnected-(U$1-PadNC1-PF7)") (class "Default")
      (node (ref "U$1") (pin "NC1-PF7") (pinfunction "NC1-PF7_NC1-PF7") (pintype "bidirectional"))
    )
    (net (code "158") (name "unconnected-(U$1-PadNC2-PF6)") (class "Default")
      (node (ref "U$1") (pin "NC2-PF6") (pinfunction "NC2-PF6_NC2-PF6") (pintype "bidirectional"))
    )
    (net (code "159") (name "unconnected-(U$1-PadNC3)") (class "Default")
      (node (ref "U$1") (pin "NC3") (pinfunction "NC3_NC3") (pintype "no_connect"))
    )
    (net (code "160") (name "unconnected-(U$1-PadNC4)") (class "Default")
      (node (ref "U$1") (pin "NC4") (pinfunction "NC4_NC4") (pintype "no_connect"))
    )
    (net (code "161") (name "unconnected-(U$1-PadNC5-PD8)") (class "Default")
      (node (ref "U$1") (pin "NC5-PD8") (pinfunction "NC5-PD8_NC5-PD8") (pintype "bidirectional"))
    )
    (net (code "162") (name "unconnected-(U$1-PadNC6-PB11)") (class "Default")
      (node (ref "U$1") (pin "NC6-PB11") (pinfunction "NC6-PB11_NC6-PB11") (pintype "no_connect"))
    )
    (net (code "163") (name "unconnected-(U$1-PadNC7-PF5)") (class "Default")
      (node (ref "U$1") (pin "NC7-PF5") (pinfunction "NC7-PF5_NC7-PF5") (pintype "bidirectional"))
    )
    (net (code "164") (name "unconnected-(U$1-PadNC8-PF4)") (class "Default")
      (node (ref "U$1") (pin "NC8-PF4") (pinfunction "NC8-PF4_NC8-PF4") (pintype "bidirectional"))
    )
    (net (code "165") (name "unconnected-(U$1-PadNRESET)") (class "Default")
      (node (ref "U$1") (pin "NRESET") (pinfunction "NRESET_NRESET") (pintype "input"))
    )
    (net (code "166") (name "unconnected-(U$1-PadPA1)") (class "Default")
      (node (ref "U$1") (pin "PA1") (pinfunction "PA1_PA1") (pintype "bidirectional"))
    )
    (net (code "167") (name "unconnected-(U$1-PadPA2)") (class "Default")
      (node (ref "U$1") (pin "PA2") (pinfunction "PA2_PA2") (pintype "bidirectional"))
    )
    (net (code "168") (name "unconnected-(U$1-PadPA3)") (class "Default")
      (node (ref "U$1") (pin "PA3") (pinfunction "PA3_PA3") (pintype "bidirectional"))
    )
    (net (code "169") (name "unconnected-(U$1-PadPA5)") (class "Default")
      (node (ref "U$1") (pin "PA5") (pinfunction "PA5_PA5") (pintype "bidirectional"))
    )
    (net (code "170") (name "unconnected-(U$1-PadPA7)") (class "Default")
      (node (ref "U$1") (pin "PA7") (pinfunction "PA7_PA7") (pintype "bidirectional"))
    )
    (net (code "171") (name "unconnected-(U$1-PadPA9)") (class "Default")
      (node (ref "U$1") (pin "PA9") (pinfunction "PA9_PA9") (pintype "bidirectional"))
    )
    (net (code "172") (name "unconnected-(U$1-PadPA10)") (class "Default")
      (node (ref "U$1") (pin "PA10") (pinfunction "PA10_PA10") (pintype "bidirectional"))
    )
    (net (code "173") (name "unconnected-(U$1-PadPA11)") (class "Default")
      (node (ref "U$1") (pin "PA11") (pinfunction "PA11_PA11") (pintype "bidirectional"))
    )
    (net (code "174") (name "unconnected-(U$1-PadPA12)") (class "Default")
      (node (ref "U$1") (pin "PA12") (pinfunction "PA12_PA12") (pintype "bidirectional"))
    )
    (net (code "175") (name "unconnected-(U$1-PadPA13)") (class "Default")
      (node (ref "U$1") (pin "PA13") (pinfunction "PA13_PA13") (pintype "bidirectional"))
    )
    (net (code "176") (name "unconnected-(U$1-PadPA14)") (class "Default")
      (node (ref "U$1") (pin "PA14") (pinfunction "PA14_PA14") (pintype "bidirectional"))
    )
    (net (code "177") (name "unconnected-(U$1-PadPB0)") (class "Default")
      (node (ref "U$1") (pin "PB0") (pinfunction "PB0_PB0") (pintype "bidirectional"))
    )
    (net (code "178") (name "unconnected-(U$1-PadPB13)") (class "Default")
      (node (ref "U$1") (pin "PB13") (pinfunction "PB13_PB13") (pintype "bidirectional"))
    )
    (net (code "179") (name "unconnected-(U$1-PadPC1)") (class "Default")
      (node (ref "U$1") (pin "PC1") (pinfunction "PC1_PC1") (pintype "bidirectional"))
    )
    (net (code "180") (name "unconnected-(U$1-PadPC4)") (class "Default")
      (node (ref "U$1") (pin "PC4") (pinfunction "PC4_PC4") (pintype "bidirectional"))
    )
    (net (code "181") (name "unconnected-(U$1-PadPC5)") (class "Default")
      (node (ref "U$1") (pin "PC5") (pinfunction "PC5_PC5") (pintype "bidirectional"))
    )
    (net (code "182") (name "unconnected-(U$1-PadPC13)") (class "Default")
      (node (ref "U$1") (pin "PC13") (pinfunction "PC13_PC13") (pintype "bidirectional"))
    )
    (net (code "183") (name "unconnected-(U$1-PadPC14)") (class "Default")
      (node (ref "U$1") (pin "PC14") (pinfunction "PC14_PC14") (pintype "bidirectional"))
    )
    (net (code "184") (name "unconnected-(U$1-PadPC15)") (class "Default")
      (node (ref "U$1") (pin "PC15") (pinfunction "PC15_PC15") (pintype "bidirectional"))
    )
    (net (code "185") (name "unconnected-(U$1-PadPF0-PH0)") (class "Default")
      (node (ref "U$1") (pin "PF0-PH0") (pinfunction "PF0-PH0_PF0-PH0") (pintype "bidirectional"))
    )
  )
)
